# screen_sch123.net
KiCad netlist of a schematic drawn in EAGLE
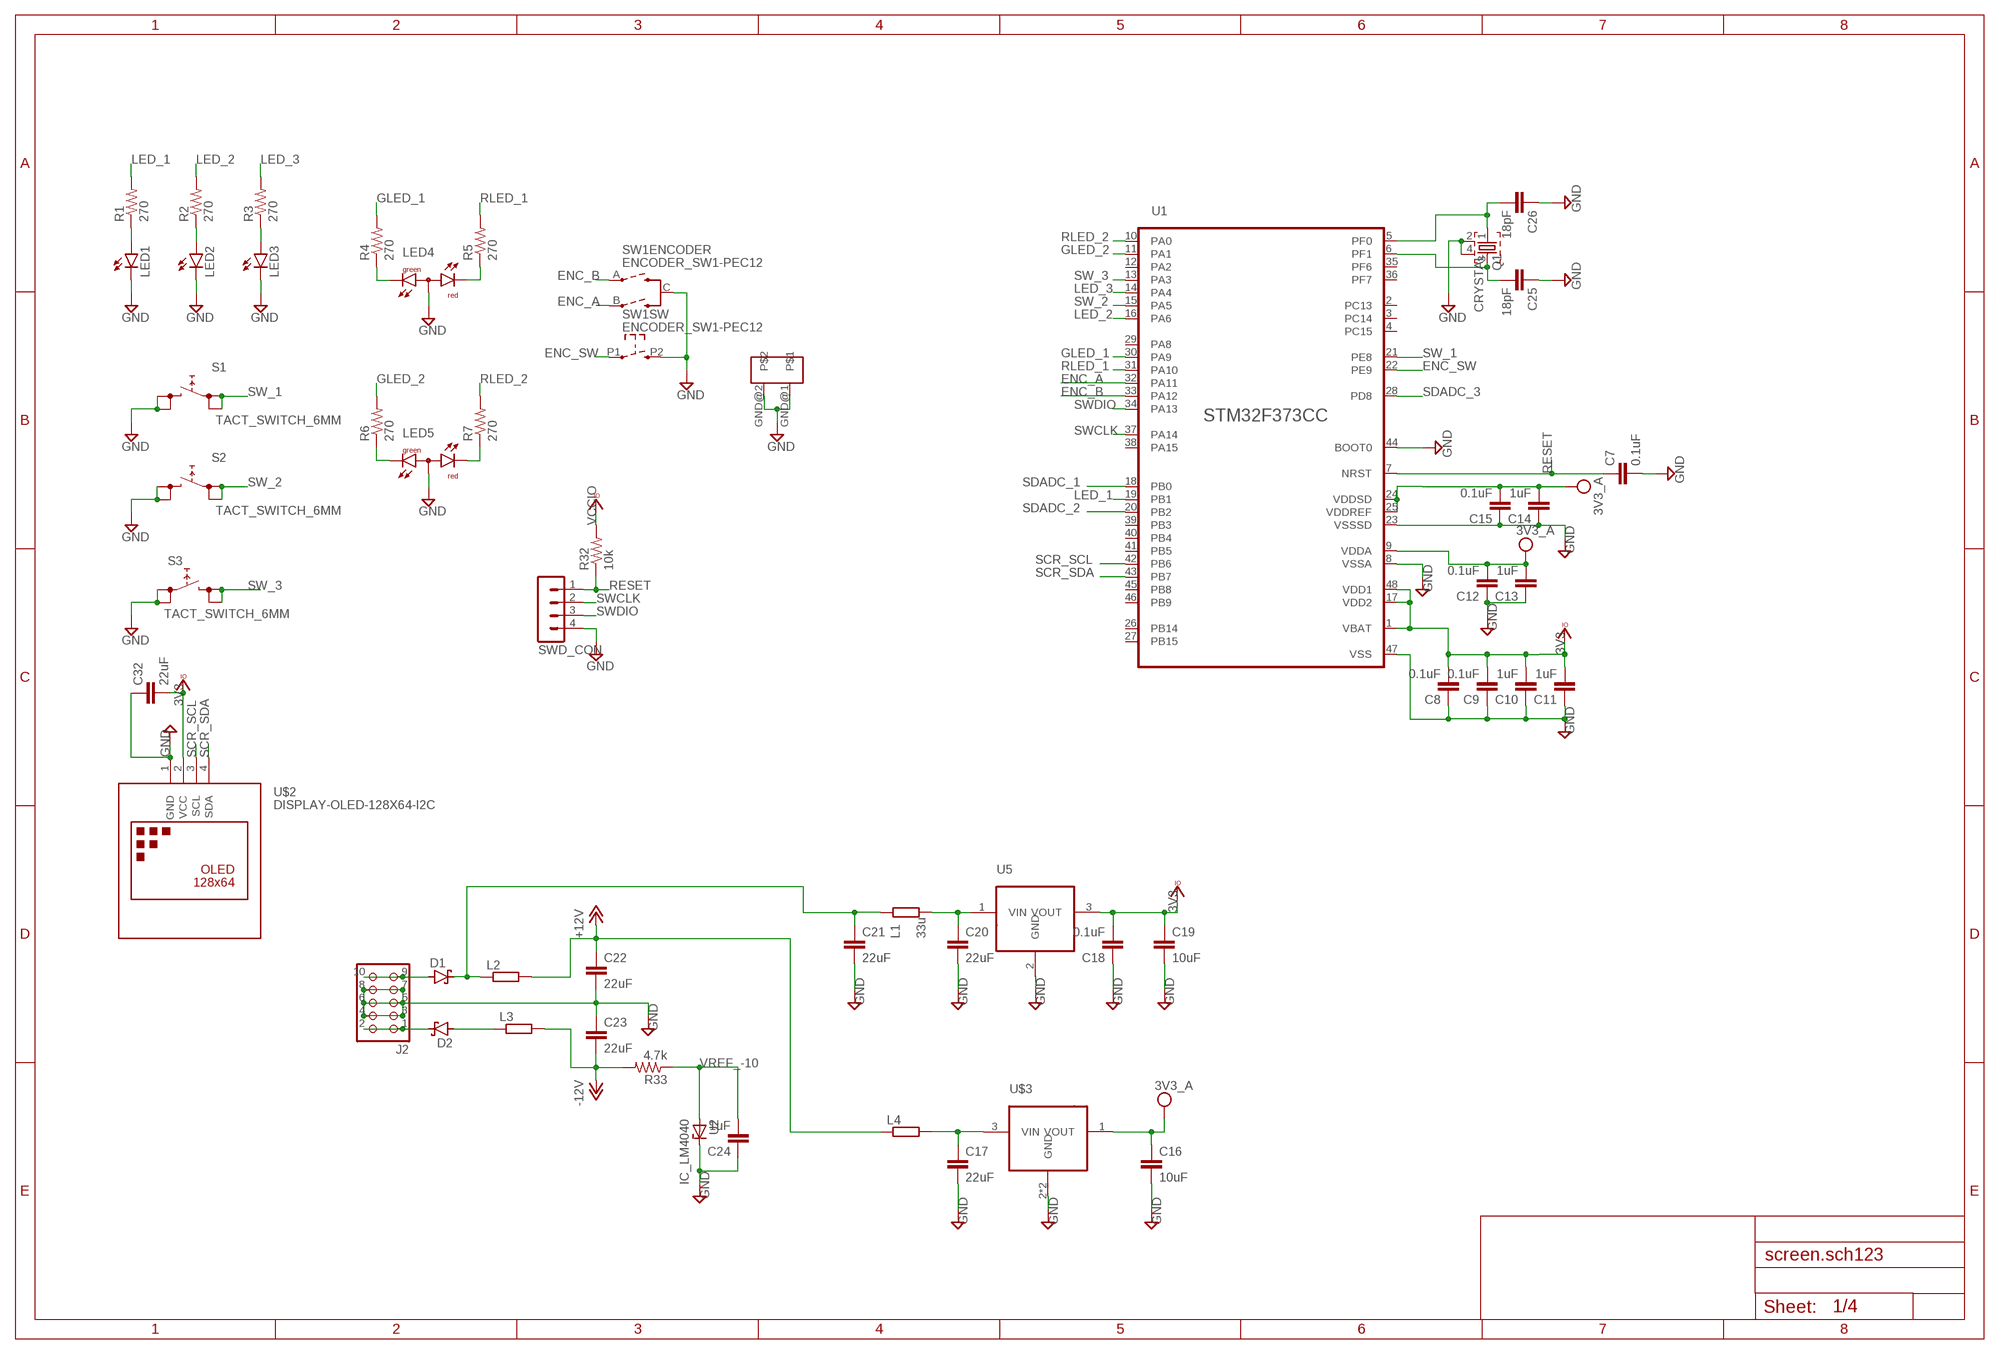
[diagram p0: schematic, sheet 1]
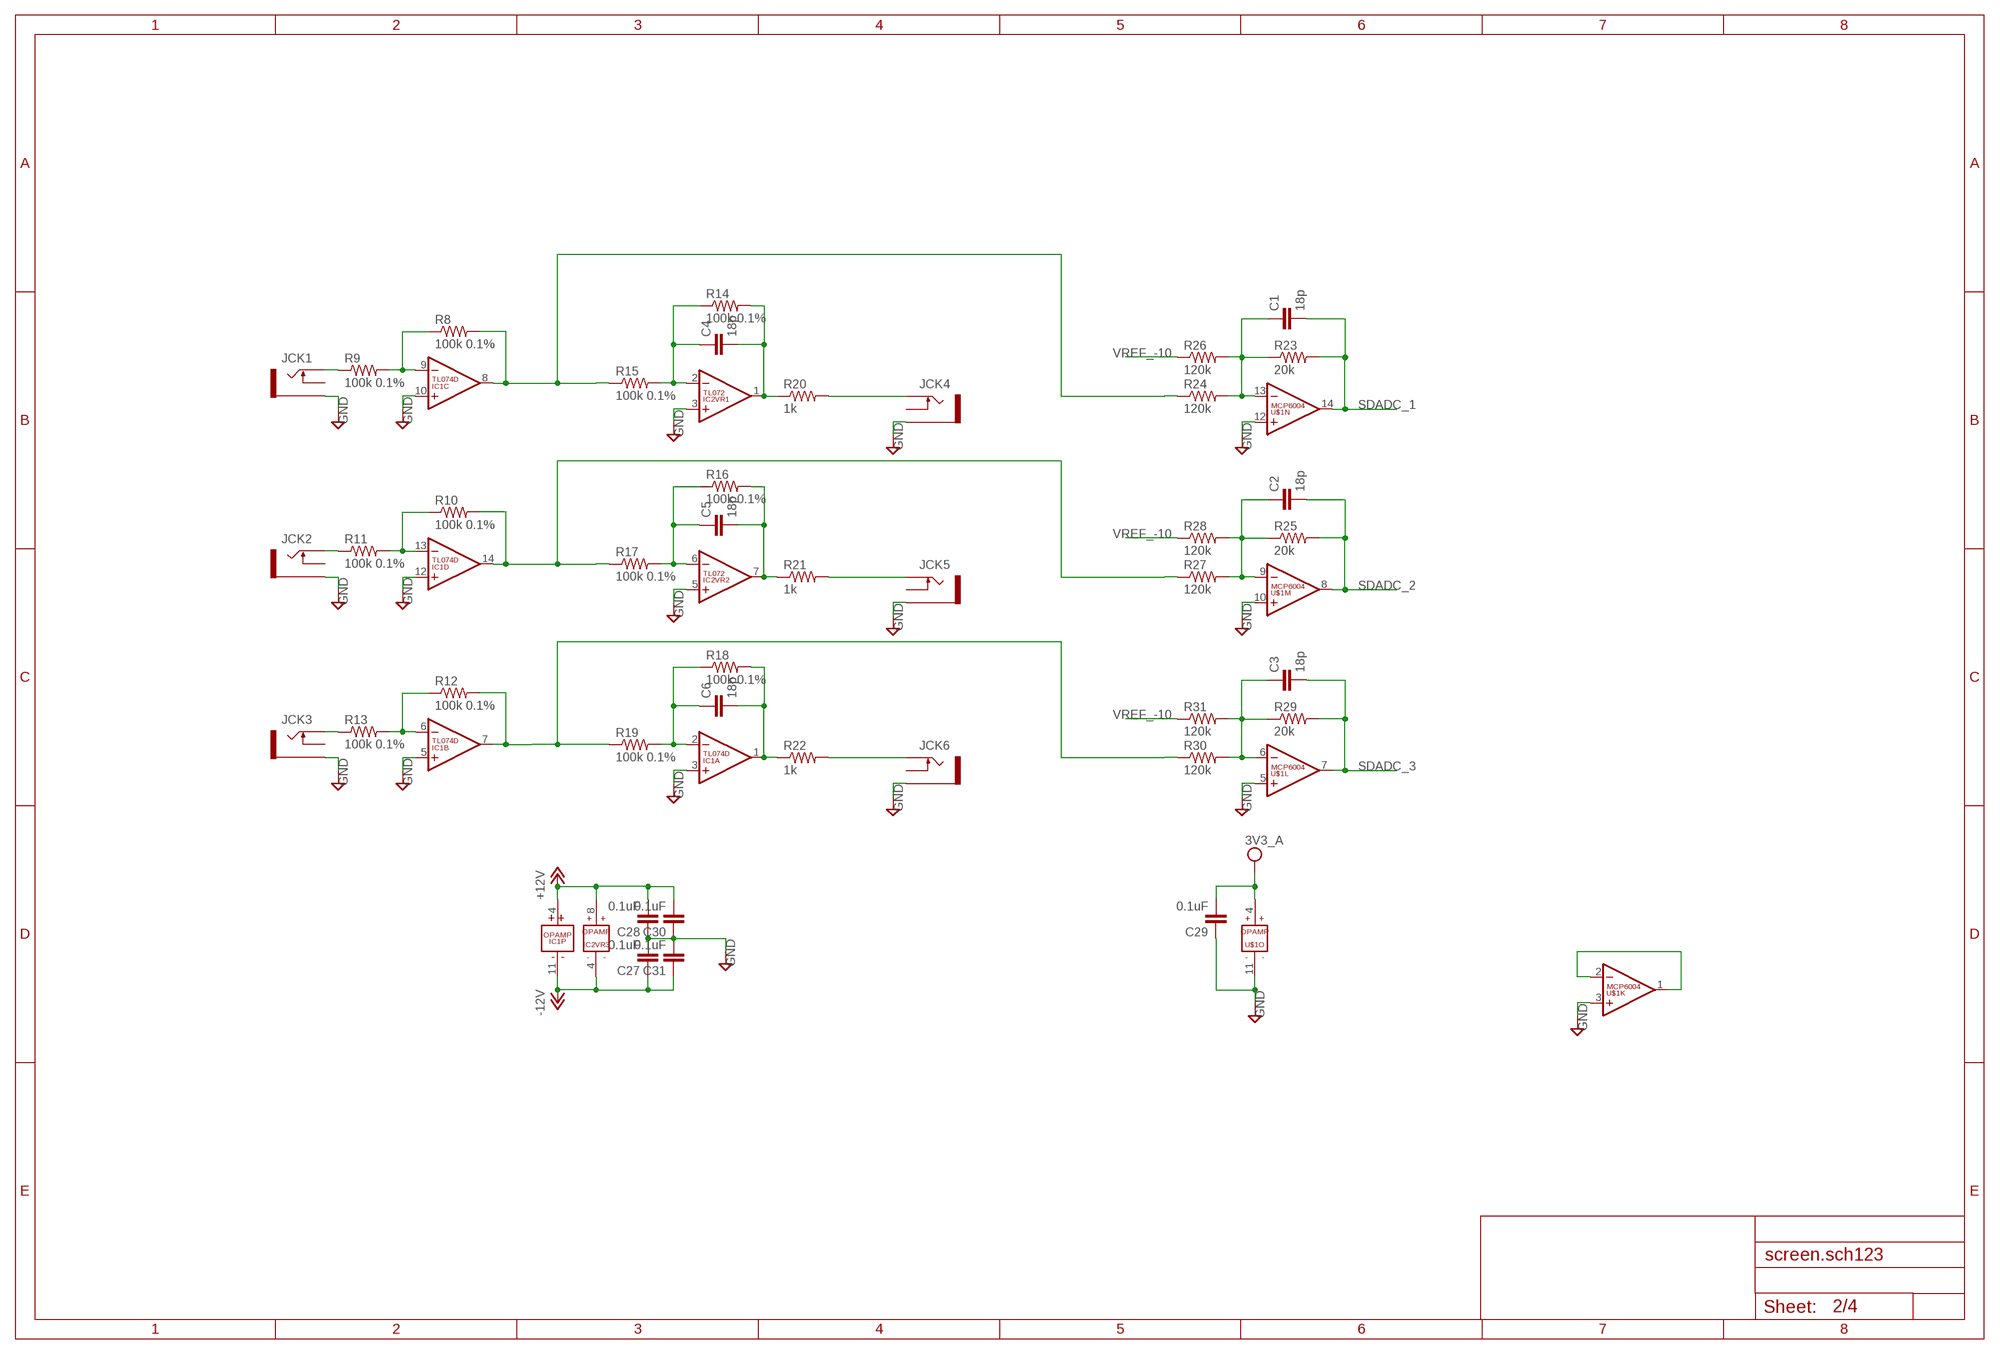
[diagram p1: schematic, sheet 2]
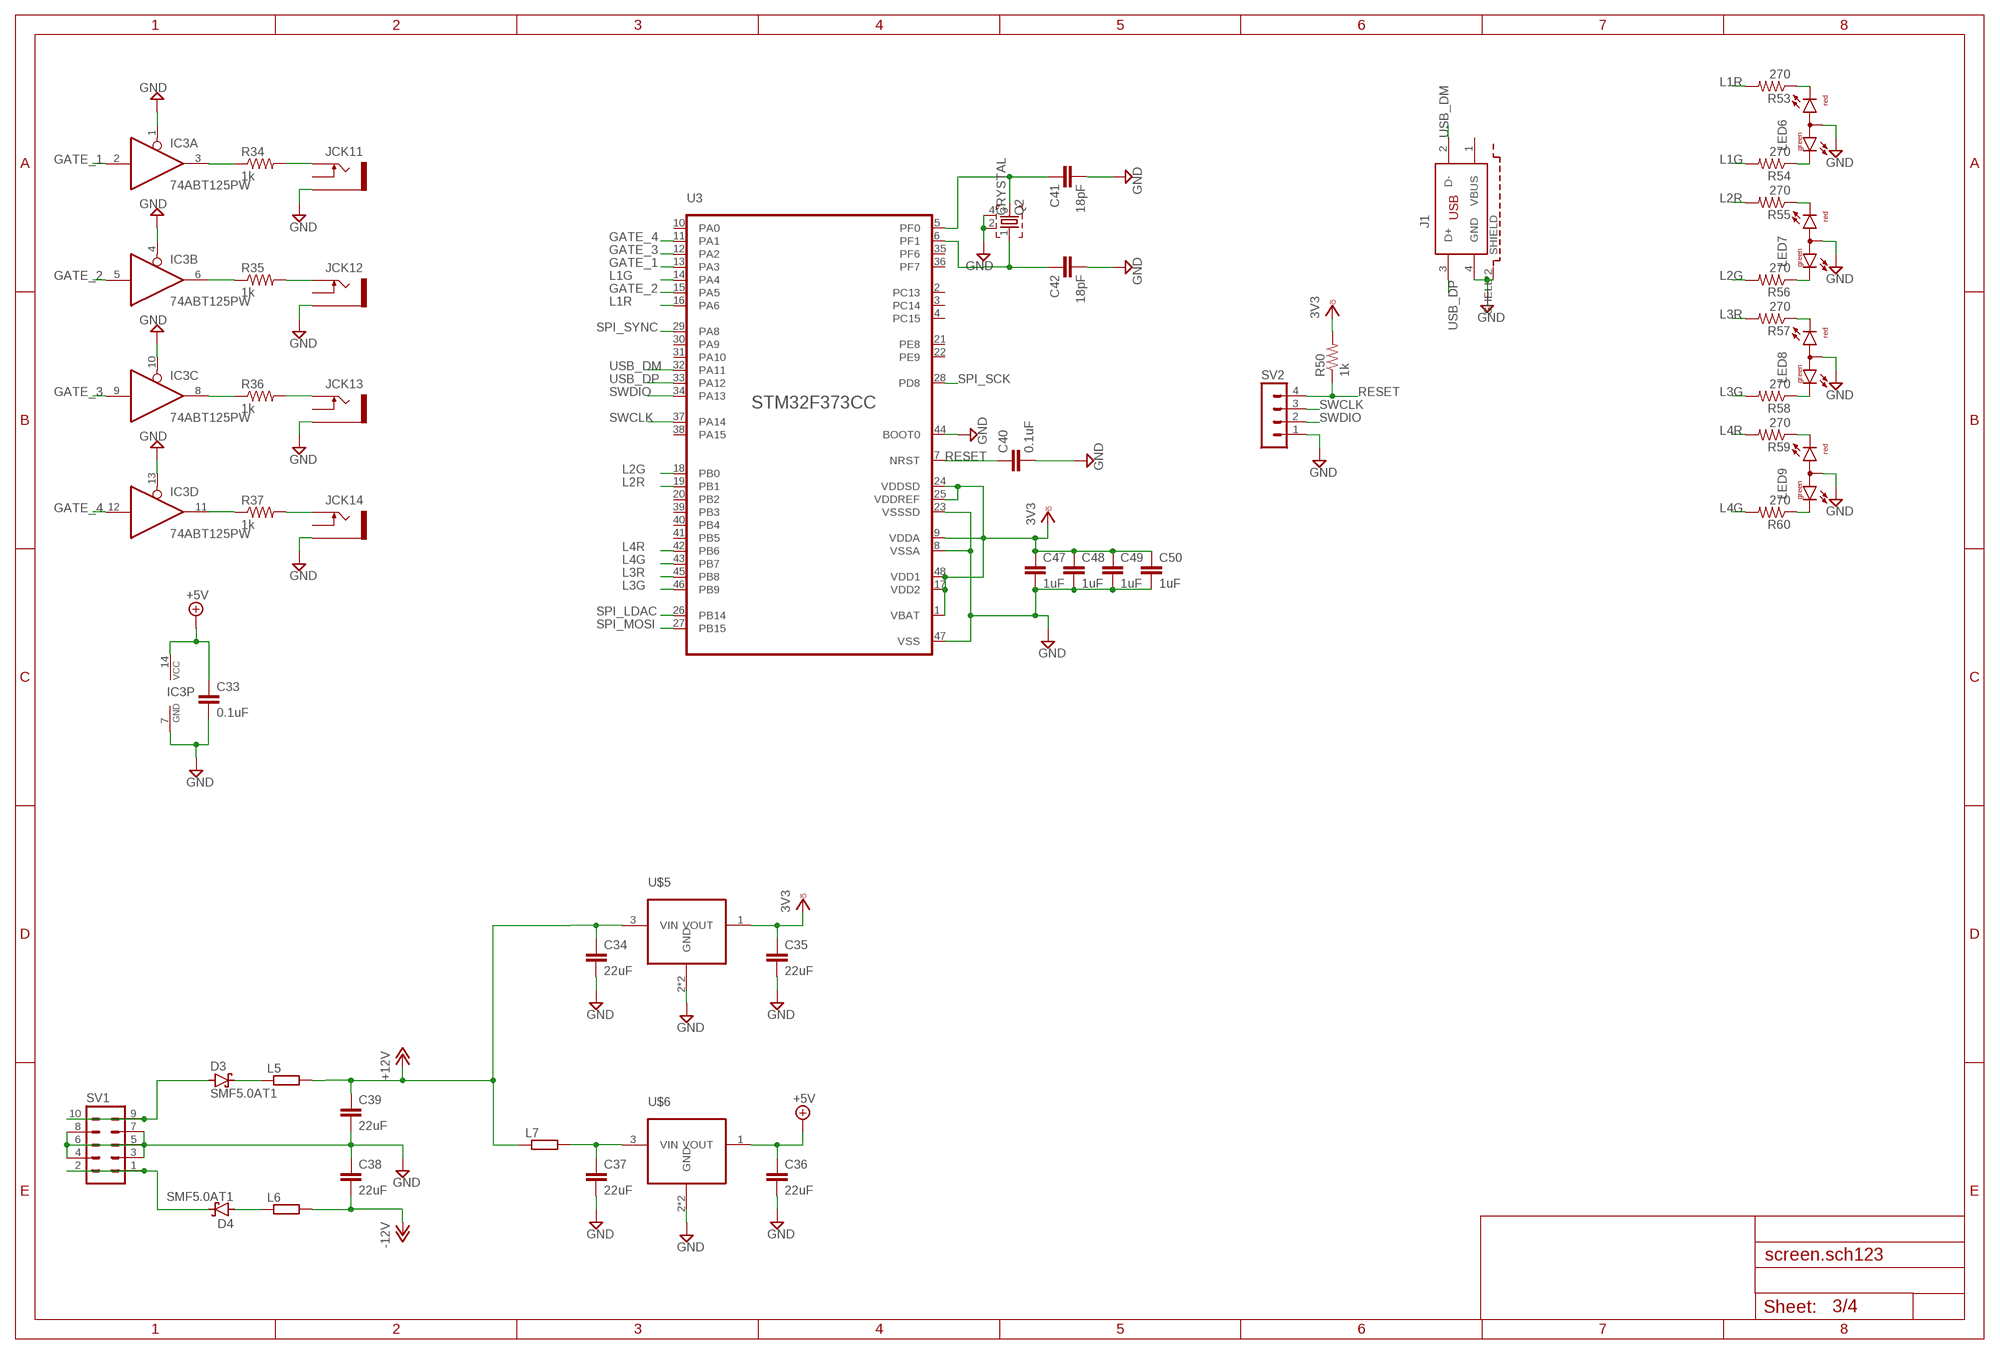
[diagram p2: schematic, sheet 3]
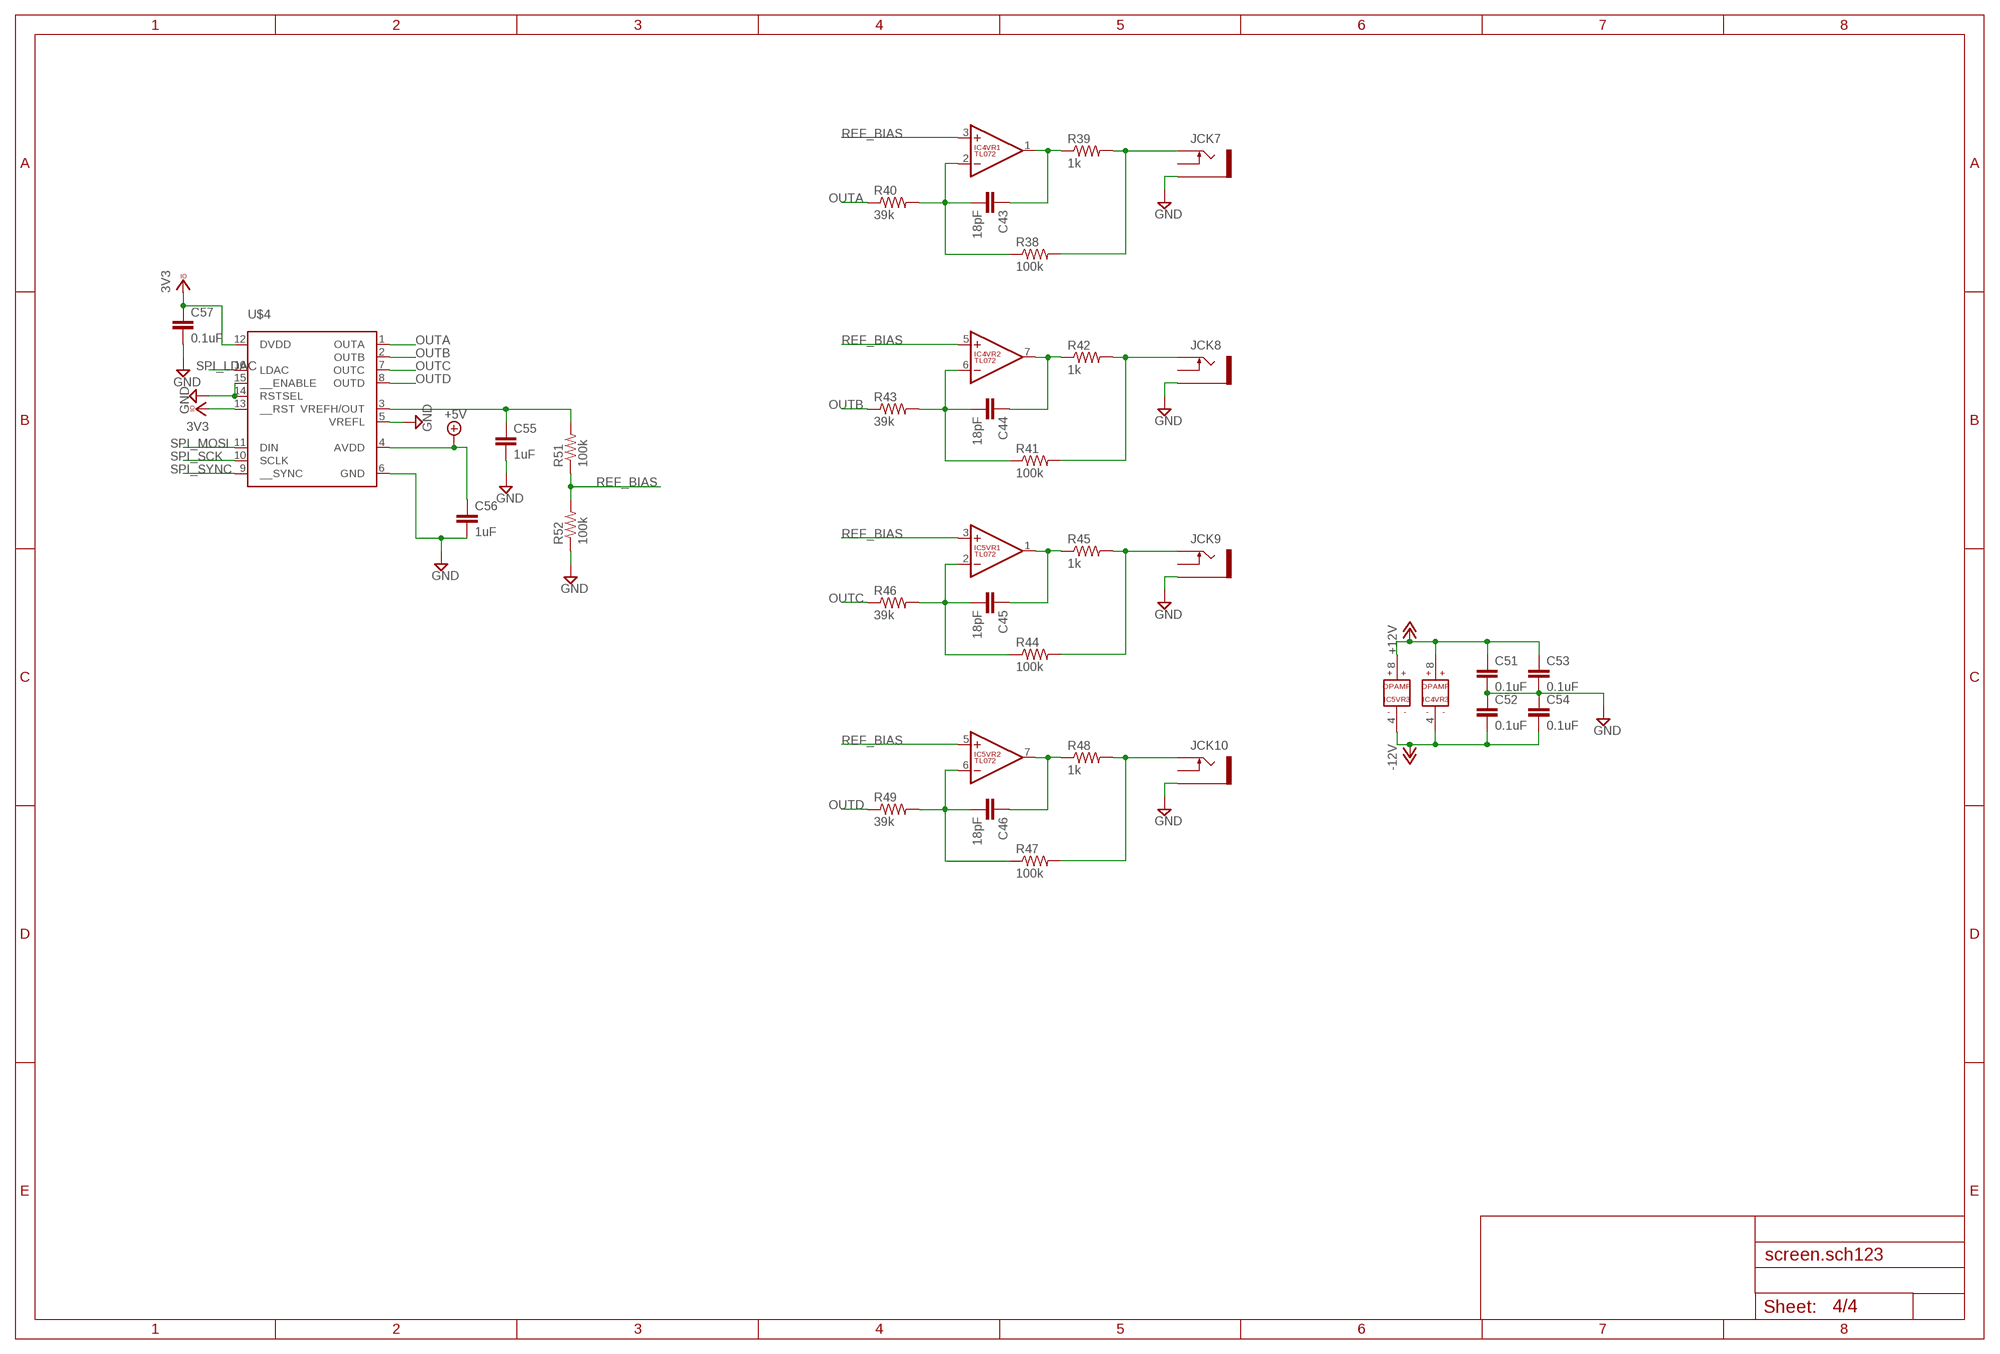
[diagram p3: schematic, sheet 4]

(export (version "E")
  (design (tool "Eeschema 10.0.6"))
  (components
    (comp (ref "C43")
      (value "18pF")
      (footprint "eagle-import:C0603K")
      (libsource (lib "eagle-import") (part "C-EUC0603K"))
    )
    (comp (ref "C44")
      (value "18pF")
      (footprint "eagle-import:C0603K")
      (libsource (lib "eagle-import") (part "C-EUC0603K"))
    )
    (comp (ref "C45")
      (value "18pF")
      (footprint "eagle-import:C0603K")
      (libsource (lib "eagle-import") (part "C-EUC0603K"))
    )
    (comp (ref "C46")
      (value "18pF")
      (footprint "eagle-import:C0603K")
      (libsource (lib "eagle-import") (part "C-EUC0603K"))
    )
    (comp (ref "C51")
      (value "0.1uF")
      (footprint "eagle-import:C0603K")
      (libsource (lib "eagle-import") (part "C-EUC0603K"))
    )
    (comp (ref "C52")
      (value "0.1uF")
      (footprint "eagle-import:C0603K")
      (libsource (lib "eagle-import") (part "C-EUC0603K"))
    )
    (comp (ref "C53")
      (value "0.1uF")
      (footprint "eagle-import:C0603K")
      (libsource (lib "eagle-import") (part "C-EUC0603K"))
    )
    (comp (ref "C54")
      (value "0.1uF")
      (footprint "eagle-import:C0603K")
      (libsource (lib "eagle-import") (part "C-EUC0603K"))
    )
    (comp (ref "C55")
      (value "1uF")
      (footprint "eagle-import:C0603K")
      (libsource (lib "eagle-import") (part "C-EUC0603K"))
    )
    (comp (ref "C56")
      (value "1uF")
      (footprint "eagle-import:C0603K")
      (libsource (lib "eagle-import") (part "C-EUC0603K"))
    )
    (comp (ref "C57")
      (value "0.1uF")
      (footprint "eagle-import:C0603K")
      (libsource (lib "eagle-import") (part "C-EUC0603K"))
    )
    (comp (ref "IC4")
      (value "TL072")
      (footprint "eagle-import:SO08")
      (libsource (lib "eagle-import") (part "TL072"))
    )
    (comp (ref "IC5")
      (value "TL072")
      (footprint "eagle-import:SO08")
      (libsource (lib "eagle-import") (part "TL072"))
    )
    (comp (ref "JCK7")
      (value "THONKICONNNEW")
      (footprint "eagle-import:WQP-PJ301M-12_JACK")
      (libsource (lib "eagle-import") (part "THONKICONNNEW"))
    )
    (comp (ref "JCK8")
      (value "THONKICONNNEW")
      (footprint "eagle-import:WQP-PJ301M-12_JACK")
      (libsource (lib "eagle-import") (part "THONKICONNNEW"))
    )
    (comp (ref "JCK9")
      (value "THONKICONNNEW")
      (footprint "eagle-import:WQP-PJ301M-12_JACK")
      (libsource (lib "eagle-import") (part "THONKICONNNEW"))
    )
    (comp (ref "JCK10")
      (value "THONKICONNNEW")
      (footprint "eagle-import:WQP-PJ301M-12_JACK")
      (libsource (lib "eagle-import") (part "THONKICONNNEW"))
    )
    (comp (ref "R38")
      (value "100k")
      (footprint "eagle-import:R0603")
      (libsource (lib "eagle-import") (part "R-US_R0603"))
    )
    (comp (ref "R39")
      (value "1k")
      (footprint "eagle-import:R0603")
      (libsource (lib "eagle-import") (part "R-US_R0603"))
    )
    (comp (ref "R40")
      (value "39k")
      (footprint "eagle-import:R0603")
      (libsource (lib "eagle-import") (part "R-US_R0603"))
    )
    (comp (ref "R41")
      (value "100k")
      (footprint "eagle-import:R0603")
      (libsource (lib "eagle-import") (part "R-US_R0603"))
    )
    (comp (ref "R42")
      (value "1k")
      (footprint "eagle-import:R0603")
      (libsource (lib "eagle-import") (part "R-US_R0603"))
    )
    (comp (ref "R43")
      (value "39k")
      (footprint "eagle-import:R0603")
      (libsource (lib "eagle-import") (part "R-US_R0603"))
    )
    (comp (ref "R44")
      (value "100k")
      (footprint "eagle-import:R0603")
      (libsource (lib "eagle-import") (part "R-US_R0603"))
    )
    (comp (ref "R45")
      (value "1k")
      (footprint "eagle-import:R0603")
      (libsource (lib "eagle-import") (part "R-US_R0603"))
    )
    (comp (ref "R46")
      (value "39k")
      (footprint "eagle-import:R0603")
      (libsource (lib "eagle-import") (part "R-US_R0603"))
    )
    (comp (ref "R47")
      (value "100k")
      (footprint "eagle-import:R0603")
      (libsource (lib "eagle-import") (part "R-US_R0603"))
    )
    (comp (ref "R48")
      (value "1k")
      (footprint "eagle-import:R0603")
      (libsource (lib "eagle-import") (part "R-US_R0603"))
    )
    (comp (ref "R49")
      (value "39k")
      (footprint "eagle-import:R0603")
      (libsource (lib "eagle-import") (part "R-US_R0603"))
    )
    (comp (ref "R51")
      (value "100k")
      (footprint "eagle-import:R0603")
      (libsource (lib "eagle-import") (part "R-US_R0603"))
    )
    (comp (ref "R52")
      (value "100k")
      (footprint "eagle-import:R0603")
      (libsource (lib "eagle-import") (part "R-US_R0603"))
    )
    (comp (ref "U$4")
      (value "DAC8565")
      (footprint "eagle-import:TSSOP16")
      (libsource (lib "eagle-import") (part "DAC8565"))
    )
    (comp (ref "C33")
      (value "0.1uF")
      (footprint "eagle-import:C0603K")
      (libsource (lib "eagle-import") (part "C-EUC0603K"))
    )
    (comp (ref "C34")
      (value "22uF")
      (footprint "eagle-import:C1206K")
      (libsource (lib "eagle-import") (part "C-EUC1206K"))
    )
    (comp (ref "C35")
      (value "22uF")
      (footprint "eagle-import:C1206K")
      (libsource (lib "eagle-import") (part "C-EUC1206K"))
    )
    (comp (ref "C36")
      (value "22uF")
      (footprint "eagle-import:C1206K")
      (libsource (lib "eagle-import") (part "C-EUC1206K"))
    )
    (comp (ref "C37")
      (value "22uF")
      (footprint "eagle-import:C1206K")
      (libsource (lib "eagle-import") (part "C-EUC1206K"))
    )
    (comp (ref "C38")
      (value "22uF")
      (footprint "eagle-import:C1206K")
      (libsource (lib "eagle-import") (part "C-EUC1206K"))
    )
    (comp (ref "C39")
      (value "22uF")
      (footprint "eagle-import:C1206K")
      (libsource (lib "eagle-import") (part "C-EUC1206K"))
    )
    (comp (ref "C40")
      (value "0.1uF")
      (footprint "eagle-import:C0603K")
      (libsource (lib "eagle-import") (part "C-EUC0603K"))
    )
    (comp (ref "C41")
      (value "18pF")
      (footprint "eagle-import:C0603K")
      (libsource (lib "eagle-import") (part "C-EUC0603K"))
    )
    (comp (ref "C42")
      (value "18pF")
      (footprint "eagle-import:C0603K")
      (libsource (lib "eagle-import") (part "C-EUC0603K"))
    )
    (comp (ref "C47")
      (value "1uF")
      (footprint "eagle-import:C0603K")
      (libsource (lib "eagle-import") (part "C-EUC0603K"))
    )
    (comp (ref "C48")
      (value "1uF")
      (footprint "eagle-import:C0603K")
      (libsource (lib "eagle-import") (part "C-EUC0603K"))
    )
    (comp (ref "C49")
      (value "1uF")
      (footprint "eagle-import:C0603K")
      (libsource (lib "eagle-import") (part "C-EUC0603K"))
    )
    (comp (ref "C50")
      (value "1uF")
      (footprint "eagle-import:C0603K")
      (libsource (lib "eagle-import") (part "C-EUC0603K"))
    )
    (comp (ref "D3")
      (value "SMF5.0AT1")
      (footprint "eagle-import:SOD123FL")
      (libsource (lib "eagle-import") (part "SMF5.0AT1"))
    )
    (comp (ref "D4")
      (value "SMF5.0AT1")
      (footprint "eagle-import:SOD123FL")
      (libsource (lib "eagle-import") (part "SMF5.0AT1"))
    )
    (comp (ref "IC3")
      (value "74ABT125PW")
      (footprint "eagle-import:TSSOP14")
      (libsource (lib "eagle-import") (part "74125PWABT"))
    )
    (comp (ref "J1")
      (value "61400413321")
      (footprint "eagle-import:61400413321")
      (libsource (lib "eagle-import") (part "61400413321"))
    )
    (comp (ref "JCK11")
      (value "THONKICONNNEW")
      (footprint "eagle-import:WQP-PJ301M-12_JACK")
      (libsource (lib "eagle-import") (part "THONKICONNNEW"))
    )
    (comp (ref "JCK12")
      (value "THONKICONNNEW")
      (footprint "eagle-import:WQP-PJ301M-12_JACK")
      (libsource (lib "eagle-import") (part "THONKICONNNEW"))
    )
    (comp (ref "JCK13")
      (value "THONKICONNNEW")
      (footprint "eagle-import:WQP-PJ301M-12_JACK")
      (libsource (lib "eagle-import") (part "THONKICONNNEW"))
    )
    (comp (ref "JCK14")
      (value "THONKICONNNEW")
      (footprint "eagle-import:WQP-PJ301M-12_JACK")
      (libsource (lib "eagle-import") (part "THONKICONNNEW"))
    )
    (comp (ref "L5")
      (value "R-EU_R0603")
      (footprint "eagle-import:R0603")
      (libsource (lib "eagle-import") (part "R-EU_R0603"))
    )
    (comp (ref "L6")
      (value "R-EU_R0603")
      (footprint "eagle-import:R0603")
      (libsource (lib "eagle-import") (part "R-EU_R0603"))
    )
    (comp (ref "L7")
      (value "R-EU_R0603")
      (footprint "eagle-import:R0603")
      (libsource (lib "eagle-import") (part "R-EU_R0603"))
    )
    (comp (ref "LED6")
      (value "L-115WEGW-CA")
      (footprint "eagle-import:DUOLED-A-3MM")
      (libsource (lib "eagle-import") (part "L-115WEGW-CA"))
    )
    (comp (ref "LED7")
      (value "L-115WEGW-CA")
      (footprint "eagle-import:DUOLED-A-3MM")
      (libsource (lib "eagle-import") (part "L-115WEGW-CA"))
    )
    (comp (ref "LED8")
      (value "L-115WEGW-CA")
      (footprint "eagle-import:DUOLED-A-3MM")
      (libsource (lib "eagle-import") (part "L-115WEGW-CA"))
    )
    (comp (ref "LED9")
      (value "L-115WEGW-CA")
      (footprint "eagle-import:DUOLED-A-3MM")
      (libsource (lib "eagle-import") (part "L-115WEGW-CA"))
    )
    (comp (ref "Q2")
      (value "CRYSTAL")
      (footprint "eagle-import:CTS406")
      (libsource (lib "eagle-import") (part "CRYSTAL"))
    )
    (comp (ref "R34")
      (value "1k")
      (footprint "eagle-import:R0603")
      (libsource (lib "eagle-import") (part "R-US_R0603"))
    )
    (comp (ref "R35")
      (value "1k")
      (footprint "eagle-import:R0603")
      (libsource (lib "eagle-import") (part "R-US_R0603"))
    )
    (comp (ref "R36")
      (value "1k")
      (footprint "eagle-import:R0603")
      (libsource (lib "eagle-import") (part "R-US_R0603"))
    )
    (comp (ref "R37")
      (value "1k")
      (footprint "eagle-import:R0603")
      (libsource (lib "eagle-import") (part "R-US_R0603"))
    )
    (comp (ref "R50")
      (value "1k")
      (footprint "eagle-import:R0603")
      (libsource (lib "eagle-import") (part "R-US_R0603"))
    )
    (comp (ref "R53")
      (value "270")
      (footprint "eagle-import:R0603")
      (libsource (lib "eagle-import") (part "R-US_R0603"))
    )
    (comp (ref "R54")
      (value "270")
      (footprint "eagle-import:R0603")
      (libsource (lib "eagle-import") (part "R-US_R0603"))
    )
    (comp (ref "R55")
      (value "270")
      (footprint "eagle-import:R0603")
      (libsource (lib "eagle-import") (part "R-US_R0603"))
    )
    (comp (ref "R56")
      (value "270")
      (footprint "eagle-import:R0603")
      (libsource (lib "eagle-import") (part "R-US_R0603"))
    )
    (comp (ref "R57")
      (value "270")
      (footprint "eagle-import:R0603")
      (libsource (lib "eagle-import") (part "R-US_R0603"))
    )
    (comp (ref "R58")
      (value "270")
      (footprint "eagle-import:R0603")
      (libsource (lib "eagle-import") (part "R-US_R0603"))
    )
    (comp (ref "R59")
      (value "270")
      (footprint "eagle-import:R0603")
      (libsource (lib "eagle-import") (part "R-US_R0603"))
    )
    (comp (ref "R60")
      (value "270")
      (footprint "eagle-import:R0603")
      (libsource (lib "eagle-import") (part "R-US_R0603"))
    )
    (comp (ref "SV1")
      (value "MA05-2")
      (footprint "eagle-import:MA05-2")
      (libsource (lib "eagle-import") (part "MA05-2"))
    )
    (comp (ref "SV2")
      (value "MA04-1")
      (footprint "eagle-import:MA04-1")
      (libsource (lib "eagle-import") (part "MA04-1"))
    )
    (comp (ref "U$5")
      (value "LD2981ABUSOT89")
      (footprint "eagle-import:SOT89")
      (libsource (lib "eagle-import") (part "LD2981ABUSOT89"))
    )
    (comp (ref "U$6")
      (value "LD2981ABUSOT89")
      (footprint "eagle-import:SOT89")
      (libsource (lib "eagle-import") (part "LD2981ABUSOT89"))
    )
    (comp (ref "U3")
      (value "STM32F373LQFP48")
      (footprint "eagle-import:LQFP48")
      (libsource (lib "eagle-import") (part "STM32F373LQFP48"))
    )
    (comp (ref "C7")
      (value "0.1uF")
      (footprint "eagle-import:C0603")
      (libsource (lib "eagle-import") (part "C-EUC0603"))
    )
    (comp (ref "C8")
      (value "0.1uF")
      (footprint "eagle-import:C0603")
      (libsource (lib "eagle-import") (part "C-EUC0603"))
    )
    (comp (ref "C9")
      (value "0.1uF")
      (footprint "eagle-import:C0603")
      (libsource (lib "eagle-import") (part "C-EUC0603"))
    )
    (comp (ref "C10")
      (value "1uF")
      (footprint "eagle-import:C0603")
      (libsource (lib "eagle-import") (part "C-EUC0603"))
    )
    (comp (ref "C11")
      (value "1uF")
      (footprint "eagle-import:C0603")
      (libsource (lib "eagle-import") (part "C-EUC0603"))
    )
    (comp (ref "C12")
      (value "0.1uF")
      (footprint "eagle-import:C0603")
      (libsource (lib "eagle-import") (part "C-EUC0603"))
    )
    (comp (ref "C13")
      (value "1uF")
      (footprint "eagle-import:C0603")
      (libsource (lib "eagle-import") (part "C-EUC0603"))
    )
    (comp (ref "C14")
      (value "1uF")
      (footprint "eagle-import:C0603")
      (libsource (lib "eagle-import") (part "C-EUC0603"))
    )
    (comp (ref "C15")
      (value "0.1uF")
      (footprint "eagle-import:C0603")
      (libsource (lib "eagle-import") (part "C-EUC0603"))
    )
    (comp (ref "C16")
      (value "10uF")
      (footprint "eagle-import:C1206")
      (libsource (lib "eagle-import") (part "C-EUC1206"))
    )
    (comp (ref "C17")
      (value "22uF")
      (footprint "eagle-import:C1206")
      (libsource (lib "eagle-import") (part "C-EUC1206"))
    )
    (comp (ref "C18")
      (value "0.1uF")
      (footprint "eagle-import:C0603")
      (libsource (lib "eagle-import") (part "C-EUC0603"))
    )
    (comp (ref "C19")
      (value "10uF")
      (footprint "eagle-import:C1206")
      (libsource (lib "eagle-import") (part "C-EUC1206"))
    )
    (comp (ref "C20")
      (value "22uF")
      (footprint "eagle-import:C1206")
      (libsource (lib "eagle-import") (part "C-EUC1206"))
    )
    (comp (ref "C21")
      (value "22uF")
      (footprint "eagle-import:C1206")
      (libsource (lib "eagle-import") (part "C-EUC1206"))
    )
    (comp (ref "C22")
      (value "22uF")
      (footprint "eagle-import:C1206")
      (libsource (lib "eagle-import") (part "C-EUC1206"))
    )
    (comp (ref "C23")
      (value "22uF")
      (footprint "eagle-import:C1206")
      (libsource (lib "eagle-import") (part "C-EUC1206"))
    )
    (comp (ref "C24")
      (value "1uF")
      (footprint "eagle-import:C0603")
      (libsource (lib "eagle-import") (part "C-EUC0603"))
    )
    (comp (ref "C25")
      (value "18pF")
      (footprint "eagle-import:C0603")
      (libsource (lib "eagle-import") (part "C-EUC0603"))
    )
    (comp (ref "C26")
      (value "18pF")
      (footprint "eagle-import:C0603")
      (libsource (lib "eagle-import") (part "C-EUC0603"))
    )
    (comp (ref "C32")
      (value "22uF")
      (footprint "eagle-import:C1206")
      (libsource (lib "eagle-import") (part "C-EUC1206"))
    )
    (comp (ref "D1")
      (value "SMF5.0AT1")
      (footprint "eagle-import:SOD123FL")
      (libsource (lib "eagle-import") (part "SMF5.0AT1"))
    )
    (comp (ref "D2")
      (value "SMF5.0AT1")
      (footprint "eagle-import:SOD123FL")
      (libsource (lib "eagle-import") (part "SMF5.0AT1"))
    )
    (comp (ref "J2")
      (value "CON_HEADER_2X05-PTH+SHROUDED_A")
      (footprint "eagle-import:PINSHRD_PTH_2X05")
      (libsource (lib "eagle-import") (part "CON_HEADER_2X05-PTH+SHROUDED_A"))
    )
    (comp (ref "L1")
      (value "33u")
      (footprint "eagle-import:R0805")
      (libsource (lib "eagle-import") (part "R-EU_R0805"))
    )
    (comp (ref "L2")
      (value "R-EU_R0603")
      (footprint "eagle-import:R0603")
      (libsource (lib "eagle-import") (part "R-EU_R0603"))
    )
    (comp (ref "L3")
      (value "R-EU_R0603")
      (footprint "eagle-import:R0603")
      (libsource (lib "eagle-import") (part "R-EU_R0603"))
    )
    (comp (ref "L4")
      (value "R-EU_R0603")
      (footprint "eagle-import:R0603")
      (libsource (lib "eagle-import") (part "R-EU_R0603"))
    )
    (comp (ref "LED1")
      (value "LED3MM")
      (footprint "eagle-import:LED3MM")
      (libsource (lib "eagle-import") (part "LED3MM"))
    )
    (comp (ref "LED2")
      (value "LED3MM")
      (footprint "eagle-import:LED3MM")
      (libsource (lib "eagle-import") (part "LED3MM"))
    )
    (comp (ref "LED3")
      (value "LED3MM")
      (footprint "eagle-import:LED3MM")
      (libsource (lib "eagle-import") (part "LED3MM"))
    )
    (comp (ref "LED4")
      (value "L-115WEGW-CA")
      (footprint "eagle-import:DUOLED-A-3MM")
      (libsource (lib "eagle-import") (part "L-115WEGW-CA"))
    )
    (comp (ref "LED5")
      (value "L-115WEGW-CA")
      (footprint "eagle-import:DUOLED-A-3MM")
      (libsource (lib "eagle-import") (part "L-115WEGW-CA"))
    )
    (comp (ref "Q1")
      (value "CRYSTAL")
      (footprint "eagle-import:CTS406")
      (libsource (lib "eagle-import") (part "CRYSTAL"))
    )
    (comp (ref "R1")
      (value "270")
      (footprint "eagle-import:R0603")
      (libsource (lib "eagle-import") (part "R-US_R0603"))
    )
    (comp (ref "R2")
      (value "270")
      (footprint "eagle-import:R0603")
      (libsource (lib "eagle-import") (part "R-US_R0603"))
    )
    (comp (ref "R3")
      (value "270")
      (footprint "eagle-import:R0603")
      (libsource (lib "eagle-import") (part "R-US_R0603"))
    )
    (comp (ref "R4")
      (value "270")
      (footprint "eagle-import:R0603")
      (libsource (lib "eagle-import") (part "R-US_R0603"))
    )
    (comp (ref "R5")
      (value "270")
      (footprint "eagle-import:R0603")
      (libsource (lib "eagle-import") (part "R-US_R0603"))
    )
    (comp (ref "R6")
      (value "270")
      (footprint "eagle-import:R0603")
      (libsource (lib "eagle-import") (part "R-US_R0603"))
    )
    (comp (ref "R7")
      (value "270")
      (footprint "eagle-import:R0603")
      (libsource (lib "eagle-import") (part "R-US_R0603"))
    )
    (comp (ref "R32")
      (value "10k")
      (footprint "eagle-import:R0603")
      (libsource (lib "eagle-import") (part "R-US_R0603"))
    )
    (comp (ref "R33")
      (value "4.7k")
      (footprint "eagle-import:R0603")
      (libsource (lib "eagle-import") (part "R-US_R0603"))
    )
    (comp (ref "S1")
      (value "TACT_SWITCH_6MM")
      (footprint "eagle-import:TACT_SWITCH_6MM")
      (libsource (lib "eagle-import") (part "TACT_SWITCH_6MM"))
    )
    (comp (ref "S2")
      (value "TACT_SWITCH_6MM")
      (footprint "eagle-import:TACT_SWITCH_6MM")
      (libsource (lib "eagle-import") (part "TACT_SWITCH_6MM"))
    )
    (comp (ref "S3")
      (value "TACT_SWITCH_6MM")
      (footprint "eagle-import:TACT_SWITCH_6MM")
      (libsource (lib "eagle-import") (part "TACT_SWITCH_6MM"))
    )
    (comp (ref "SW1")
      (value "ENCODER_SW1-PEC12")
      (footprint "eagle-import:PEC12_INCREMENTAL_ENCODER")
      (libsource (lib "eagle-import") (part "ENCODER_SW1-PEC12"))
    )
    (comp (ref "SWD_CON")
      (value "MA04-1")
      (footprint "eagle-import:MA04-1")
      (libsource (lib "eagle-import") (part "MA04-1"))
    )
    (comp (ref "U$2")
      (value "DISPLAY-OLED-128X64-I2C")
      (footprint "eagle-import:DISPLAY-OLED-128X64-I2C")
      (libsource (lib "eagle-import") (part "DISPLAY-OLED-128X64-I2C"))
    )
    (comp (ref "U$3")
      (value "LD2981ABUSOT89")
      (footprint "eagle-import:SOT89")
      (libsource (lib "eagle-import") (part "LD2981ABUSOT89"))
    )
    (comp (ref "U1")
      (value "STM32F373LQFP48")
      (footprint "eagle-import:LQFP48")
      (libsource (lib "eagle-import") (part "STM32F373LQFP48"))
    )
    (comp (ref "U2")
      (value "IC_LM4040")
      (footprint "eagle-import:SOT-23")
      (libsource (lib "eagle-import") (part "IC_LM4040"))
    )
    (comp (ref "U5")
      (value "R-78E-0.5")
      (footprint "eagle-import:TO-220_RECOM")
      (libsource (lib "eagle-import") (part "R-78E-0.5"))
    )
    (comp (ref "C1")
      (value "18p")
      (footprint "eagle-import:C0603")
      (libsource (lib "eagle-import") (part "C-EUC0603"))
    )
    (comp (ref "C2")
      (value "18p")
      (footprint "eagle-import:C0603")
      (libsource (lib "eagle-import") (part "C-EUC0603"))
    )
    (comp (ref "C3")
      (value "18p")
      (footprint "eagle-import:C0603")
      (libsource (lib "eagle-import") (part "C-EUC0603"))
    )
    (comp (ref "C4")
      (value "18p")
      (footprint "eagle-import:C0603")
      (libsource (lib "eagle-import") (part "C-EUC0603"))
    )
    (comp (ref "C5")
      (value "18p")
      (footprint "eagle-import:C0603")
      (libsource (lib "eagle-import") (part "C-EUC0603"))
    )
    (comp (ref "C6")
      (value "18p")
      (footprint "eagle-import:C0603")
      (libsource (lib "eagle-import") (part "C-EUC0603"))
    )
    (comp (ref "C27")
      (value "0.1uF")
      (footprint "eagle-import:C0603")
      (libsource (lib "eagle-import") (part "C-EUC0603"))
    )
    (comp (ref "C28")
      (value "0.1uF")
      (footprint "eagle-import:C0603")
      (libsource (lib "eagle-import") (part "C-EUC0603"))
    )
    (comp (ref "C29")
      (value "0.1uF")
      (footprint "eagle-import:C0603")
      (libsource (lib "eagle-import") (part "C-EUC0603"))
    )
    (comp (ref "C30")
      (value "0.1uF")
      (footprint "eagle-import:C0603")
      (libsource (lib "eagle-import") (part "C-EUC0603"))
    )
    (comp (ref "C31")
      (value "0.1uF")
      (footprint "eagle-import:C0603")
      (libsource (lib "eagle-import") (part "C-EUC0603"))
    )
    (comp (ref "IC1")
      (value "TL074D")
      (footprint "eagle-import:SO14")
      (libsource (lib "eagle-import") (part "TL074D"))
    )
    (comp (ref "IC2")
      (value "TL072")
      (footprint "eagle-import:SO08")
      (libsource (lib "eagle-import") (part "TL072"))
    )
    (comp (ref "JCK1")
      (value "THONKICONNNEW")
      (footprint "eagle-import:WQP-PJ301M-12_JACK")
      (libsource (lib "eagle-import") (part "THONKICONNNEW"))
    )
    (comp (ref "JCK2")
      (value "THONKICONNNEW")
      (footprint "eagle-import:WQP-PJ301M-12_JACK")
      (libsource (lib "eagle-import") (part "THONKICONNNEW"))
    )
    (comp (ref "JCK3")
      (value "THONKICONNNEW")
      (footprint "eagle-import:WQP-PJ301M-12_JACK")
      (libsource (lib "eagle-import") (part "THONKICONNNEW"))
    )
    (comp (ref "JCK4")
      (value "THONKICONNNEW")
      (footprint "eagle-import:WQP-PJ301M-12_JACK")
      (libsource (lib "eagle-import") (part "THONKICONNNEW"))
    )
    (comp (ref "JCK5")
      (value "THONKICONNNEW")
      (footprint "eagle-import:WQP-PJ301M-12_JACK")
      (libsource (lib "eagle-import") (part "THONKICONNNEW"))
    )
    (comp (ref "JCK6")
      (value "THONKICONNNEW")
      (footprint "eagle-import:WQP-PJ301M-12_JACK")
      (libsource (lib "eagle-import") (part "THONKICONNNEW"))
    )
    (comp (ref "R8")
      (value "100k 0.1%")
      (footprint "eagle-import:R0603")
      (libsource (lib "eagle-import") (part "R-US_R0603"))
    )
    (comp (ref "R9")
      (value "100k 0.1%")
      (footprint "eagle-import:R0603")
      (libsource (lib "eagle-import") (part "R-US_R0603"))
    )
    (comp (ref "R10")
      (value "100k 0.1%")
      (footprint "eagle-import:R0603")
      (libsource (lib "eagle-import") (part "R-US_R0603"))
    )
    (comp (ref "R11")
      (value "100k 0.1%")
      (footprint "eagle-import:R0603")
      (libsource (lib "eagle-import") (part "R-US_R0603"))
    )
    (comp (ref "R12")
      (value "100k 0.1%")
      (footprint "eagle-import:R0603")
      (libsource (lib "eagle-import") (part "R-US_R0603"))
    )
    (comp (ref "R13")
      (value "100k 0.1%")
      (footprint "eagle-import:R0603")
      (libsource (lib "eagle-import") (part "R-US_R0603"))
    )
    (comp (ref "R14")
      (value "100k 0.1%")
      (footprint "eagle-import:R0603")
      (libsource (lib "eagle-import") (part "R-US_R0603"))
    )
    (comp (ref "R15")
      (value "100k 0.1%")
      (footprint "eagle-import:R0603")
      (libsource (lib "eagle-import") (part "R-US_R0603"))
    )
    (comp (ref "R16")
      (value "100k 0.1%")
      (footprint "eagle-import:R0603")
      (libsource (lib "eagle-import") (part "R-US_R0603"))
    )
    (comp (ref "R17")
      (value "100k 0.1%")
      (footprint "eagle-import:R0603")
      (libsource (lib "eagle-import") (part "R-US_R0603"))
    )
    (comp (ref "R18")
      (value "100k 0.1%")
      (footprint "eagle-import:R0603")
      (libsource (lib "eagle-import") (part "R-US_R0603"))
    )
    (comp (ref "R19")
      (value "100k 0.1%")
      (footprint "eagle-import:R0603")
      (libsource (lib "eagle-import") (part "R-US_R0603"))
    )
    (comp (ref "R20")
      (value "1k")
      (footprint "eagle-import:R0603")
      (libsource (lib "eagle-import") (part "R-US_R0603"))
    )
    (comp (ref "R21")
      (value "1k")
      (footprint "eagle-import:R0603")
      (libsource (lib "eagle-import") (part "R-US_R0603"))
    )
    (comp (ref "R22")
      (value "1k")
      (footprint "eagle-import:R0603")
      (libsource (lib "eagle-import") (part "R-US_R0603"))
    )
    (comp (ref "R23")
      (value "20k")
      (footprint "eagle-import:R0603")
      (libsource (lib "eagle-import") (part "R-US_R0603"))
    )
    (comp (ref "R24")
      (value "120k")
      (footprint "eagle-import:R0603")
      (libsource (lib "eagle-import") (part "R-US_R0603"))
    )
    (comp (ref "R25")
      (value "20k")
      (footprint "eagle-import:R0603")
      (libsource (lib "eagle-import") (part "R-US_R0603"))
    )
    (comp (ref "R26")
      (value "120k")
      (footprint "eagle-import:R0603")
      (libsource (lib "eagle-import") (part "R-US_R0603"))
    )
    (comp (ref "R27")
      (value "120k")
      (footprint "eagle-import:R0603")
      (libsource (lib "eagle-import") (part "R-US_R0603"))
    )
    (comp (ref "R28")
      (value "120k")
      (footprint "eagle-import:R0603")
      (libsource (lib "eagle-import") (part "R-US_R0603"))
    )
    (comp (ref "R29")
      (value "20k")
      (footprint "eagle-import:R0603")
      (libsource (lib "eagle-import") (part "R-US_R0603"))
    )
    (comp (ref "R30")
      (value "120k")
      (footprint "eagle-import:R0603")
      (libsource (lib "eagle-import") (part "R-US_R0603"))
    )
    (comp (ref "R31")
      (value "120k")
      (footprint "eagle-import:R0603")
      (libsource (lib "eagle-import") (part "R-US_R0603"))
    )
    (comp (ref "U$1")
      (value "MCP6004")
      (footprint "eagle-import:SO14")
      (libsource (lib "eagle-import") (part "MCP6004"))
    )
  )
  (nets
    (net (code "1") (name "+5V") (class "Default")
      (node (ref "C33") (pin "1") (pinfunction "1_1") (pintype "passive"))
      (node (ref "C36") (pin "1") (pinfunction "1_1") (pintype "passive"))
      (node (ref "C56") (pin "1") (pinfunction "1_1") (pintype "passive"))
      (node (ref "IC3") (pin "14") (pinfunction "VCC_14") (pintype "power_in"))
      (node (ref "U$4") (pin "4") (pinfunction "AVDD_4") (pintype "bidirectional"))
      (node (ref "U$6") (pin "1") (pinfunction "VOUT_1") (pintype "bidirectional"))
    )
    (net (code "2") (name "+12V") (class "Default")
      (node (ref "C22") (pin "1") (pinfunction "1_1") (pintype "passive"))
      (node (ref "C28") (pin "2") (pinfunction "2_2") (pintype "passive"))
      (node (ref "C30") (pin "2") (pinfunction "2_2") (pintype "passive"))
      (node (ref "C34") (pin "1") (pinfunction "1_1") (pintype "passive"))
      (node (ref "C39") (pin "1") (pinfunction "1_1") (pintype "passive"))
      (node (ref "C51") (pin "1") (pinfunction "1_1") (pintype "passive"))
      (node (ref "C53") (pin "1") (pinfunction "1_1") (pintype "passive"))
      (node (ref "IC1") (pin "4") (pinfunction "V+_4") (pintype "power_in"))
      (node (ref "IC2") (pin "8") (pinfunction "V+_8") (pintype "power_in"))
      (node (ref "IC4") (pin "8") (pinfunction "V+_8") (pintype "power_in"))
      (node (ref "IC5") (pin "8") (pinfunction "V+_8") (pintype "power_in"))
      (node (ref "L2") (pin "2") (pinfunction "2_2") (pintype "passive"))
      (node (ref "L4") (pin "1") (pinfunction "1_1") (pintype "passive"))
      (node (ref "L5") (pin "2") (pinfunction "2_2") (pintype "passive"))
      (node (ref "L7") (pin "1") (pinfunction "1_1") (pintype "passive"))
      (node (ref "U$5") (pin "3") (pinfunction "VIN_3") (pintype "bidirectional"))
    )
    (net (code "3") (name "-12V") (class "Default")
      (node (ref "C23") (pin "2") (pinfunction "2_2") (pintype "passive"))
      (node (ref "C27") (pin "1") (pinfunction "1_1") (pintype "passive"))
      (node (ref "C31") (pin "1") (pinfunction "1_1") (pintype "passive"))
      (node (ref "C38") (pin "2") (pinfunction "2_2") (pintype "passive"))
      (node (ref "C52") (pin "2") (pinfunction "2_2") (pintype "passive"))
      (node (ref "C54") (pin "2") (pinfunction "2_2") (pintype "passive"))
      (node (ref "IC1") (pin "11") (pinfunction "V-_11") (pintype "power_in"))
      (node (ref "IC2") (pin "4") (pinfunction "V-_4") (pintype "power_in"))
      (node (ref "IC4") (pin "4") (pinfunction "V-_4") (pintype "power_in"))
      (node (ref "IC5") (pin "4") (pinfunction "V-_4") (pintype "power_in"))
      (node (ref "L3") (pin "2") (pinfunction "2_2") (pintype "passive"))
      (node (ref "L6") (pin "2") (pinfunction "2_2") (pintype "passive"))
      (node (ref "R33") (pin "2") (pinfunction "2_2") (pintype "passive"))
    )
    (net (code "4") (name "ENC_A") (class "Default")
      (node (ref "SW1") (pin "B") (pinfunction "B_B") (pintype "passive"))
      (node (ref "U1") (pin "32") (pinfunction "PA11_32") (pintype "bidirectional"))
    )
    (net (code "5") (name "ENC_B") (class "Default")
      (node (ref "SW1") (pin "A") (pinfunction "A_A") (pintype "passive"))
      (node (ref "U1") (pin "33") (pinfunction "PA12_33") (pintype "bidirectional"))
    )
    (net (code "6") (name "ENC_SW") (class "Default")
      (node (ref "SW1") (pin "P1") (pinfunction "1_P1") (pintype "passive"))
      (node (ref "U1") (pin "22") (pinfunction "PE9_22") (pintype "bidirectional"))
    )
    (net (code "7") (name "GATE_1") (class "Default")
      (node (ref "IC3") (pin "2") (pinfunction "I_2") (pintype "input"))
      (node (ref "U3") (pin "13") (pinfunction "PA3_13") (pintype "bidirectional"))
    )
    (net (code "8") (name "GATE_2") (class "Default")
      (node (ref "IC3") (pin "5") (pinfunction "I_5") (pintype "input"))
      (node (ref "U3") (pin "15") (pinfunction "PA5_15") (pintype "bidirectional"))
    )
    (net (code "9") (name "GATE_3") (class "Default")
      (node (ref "IC3") (pin "9") (pinfunction "I_9") (pintype "input"))
      (node (ref "U3") (pin "12") (pinfunction "PA2_12") (pintype "bidirectional"))
    )
    (net (code "10") (name "GATE_4") (class "Default")
      (node (ref "IC3") (pin "12") (pinfunction "I_12") (pintype "input"))
      (node (ref "U3") (pin "11") (pinfunction "PA1_11") (pintype "bidirectional"))
    )
    (net (code "11") (name "GLED_1") (class "Default")
      (node (ref "R4") (pin "2") (pinfunction "2_2") (pintype "passive"))
      (node (ref "U1") (pin "30") (pinfunction "PA9_30") (pintype "bidirectional"))
    )
    (net (code "12") (name "GLED_2") (class "Default")
      (node (ref "R6") (pin "2") (pinfunction "2_2") (pintype "passive"))
      (node (ref "U1") (pin "11") (pinfunction "PA1_11") (pintype "bidirectional"))
    )
    (net (code "13") (name "GND") (class "Default")
      (node (ref "C10") (pin "1") (pinfunction "1_1") (pintype "passive"))
      (node (ref "C11") (pin "1") (pinfunction "1_1") (pintype "passive"))
      (node (ref "C12") (pin "1") (pinfunction "1_1") (pintype "passive"))
      (node (ref "C13") (pin "1") (pinfunction "1_1") (pintype "passive"))
      (node (ref "C14") (pin "1") (pinfunction "1_1") (pintype "passive"))
      (node (ref "C15") (pin "1") (pinfunction "1_1") (pintype "passive"))
      (node (ref "C16") (pin "2") (pinfunction "2_2") (pintype "passive"))
      (node (ref "C17") (pin "2") (pinfunction "2_2") (pintype "passive"))
      (node (ref "C18") (pin "1") (pinfunction "1_1") (pintype "passive"))
      (node (ref "C19") (pin "2") (pinfunction "2_2") (pintype "passive"))
      (node (ref "C20") (pin "2") (pinfunction "2_2") (pintype "passive"))
      (node (ref "C21") (pin "2") (pinfunction "2_2") (pintype "passive"))
      (node (ref "C22") (pin "2") (pinfunction "2_2") (pintype "passive"))
      (node (ref "C23") (pin "1") (pinfunction "1_1") (pintype "passive"))
      (node (ref "C24") (pin "1") (pinfunction "1_1") (pintype "passive"))
      (node (ref "C25") (pin "1") (pinfunction "1_1") (pintype "passive"))
      (node (ref "C26") (pin "1") (pinfunction "1_1") (pintype "passive"))
      (node (ref "C27") (pin "2") (pinfunction "2_2") (pintype "passive"))
      (node (ref "C28") (pin "1") (pinfunction "1_1") (pintype "passive"))
      (node (ref "C29") (pin "1") (pinfunction "1_1") (pintype "passive"))
      (node (ref "C30") (pin "1") (pinfunction "1_1") (pintype "passive"))
      (node (ref "C31") (pin "2") (pinfunction "2_2") (pintype "passive"))
      (node (ref "C32") (pin "1") (pinfunction "1_1") (pintype "passive"))
      (node (ref "C33") (pin "2") (pinfunction "2_2") (pintype "passive"))
      (node (ref "C34") (pin "2") (pinfunction "2_2") (pintype "passive"))
      (node (ref "C35") (pin "2") (pinfunction "2_2") (pintype "passive"))
      (node (ref "C36") (pin "2") (pinfunction "2_2") (pintype "passive"))
      (node (ref "C37") (pin "2") (pinfunction "2_2") (pintype "passive"))
      (node (ref "C38") (pin "1") (pinfunction "1_1") (pintype "passive"))
      (node (ref "C39") (pin "2") (pinfunction "2_2") (pintype "passive"))
      (node (ref "C40") (pin "2") (pinfunction "2_2") (pintype "passive"))
      (node (ref "C41") (pin "2") (pinfunction "2_2") (pintype "passive"))
      (node (ref "C42") (pin "2") (pinfunction "2_2") (pintype "passive"))
      (node (ref "C47") (pin "2") (pinfunction "2_2") (pintype "passive"))
      (node (ref "C48") (pin "2") (pinfunction "2_2") (pintype "passive"))
      (node (ref "C49") (pin "2") (pinfunction "2_2") (pintype "passive"))
      (node (ref "C50") (pin "2") (pinfunction "2_2") (pintype "passive"))
      (node (ref "C51") (pin "2") (pinfunction "2_2") (pintype "passive"))
      (node (ref "C52") (pin "1") (pinfunction "1_1") (pintype "passive"))
      (node (ref "C53") (pin "2") (pinfunction "2_2") (pintype "passive"))
      (node (ref "C54") (pin "1") (pinfunction "1_1") (pintype "passive"))
      (node (ref "C55") (pin "2") (pinfunction "2_2") (pintype "passive"))
      (node (ref "C56") (pin "2") (pinfunction "2_2") (pintype "passive"))
      (node (ref "C57") (pin "2") (pinfunction "2_2") (pintype "passive"))
      (node (ref "C7") (pin "2") (pinfunction "2_2") (pintype "passive"))
      (node (ref "C8") (pin "1") (pinfunction "1_1") (pintype "passive"))
      (node (ref "C9") (pin "1") (pinfunction "1_1") (pintype "passive"))
      (node (ref "IC1") (pin "10") (pinfunction "+IN_10") (pintype "input"))
      (node (ref "IC1") (pin "12") (pinfunction "+IN_12") (pintype "input"))
      (node (ref "IC1") (pin "3") (pinfunction "+IN_3") (pintype "input"))
      (node (ref "IC1") (pin "5") (pinfunction "+IN_5") (pintype "input"))
      (node (ref "IC2") (pin "3") (pinfunction "+IN_3") (pintype "input"))
      (node (ref "IC2") (pin "5") (pinfunction "+IN_5") (pintype "input"))
      (node (ref "IC3") (pin "1") (pinfunction "OE_1") (pintype "input"))
      (node (ref "IC3") (pin "10") (pinfunction "OE_10") (pintype "input"))
      (node (ref "IC3") (pin "13") (pinfunction "OE_13") (pintype "input"))
      (node (ref "IC3") (pin "4") (pinfunction "OE_4") (pintype "input"))
      (node (ref "IC3") (pin "7") (pinfunction "GND_7") (pintype "power_in"))
      (node (ref "J1") (pin "4") (pinfunction "GND_4") (pintype "bidirectional"))
      (node (ref "J1") (pin "SHELL") (pinfunction "SHIELD_SHELL") (pintype "bidirectional"))
      (node (ref "J1") (pin "SHELL1") (pinfunction "SHIELD_SHELL1") (pintype "bidirectional"))
      (node (ref "J2") (pin "3") (pinfunction "3_3") (pintype "passive"))
      (node (ref "J2") (pin "4") (pinfunction "4_4") (pintype "passive"))
      (node (ref "J2") (pin "5") (pinfunction "5_5") (pintype "passive"))
      (node (ref "J2") (pin "6") (pinfunction "6_6") (pintype "passive"))
      (node (ref "J2") (pin "7") (pinfunction "7_7") (pintype "passive"))
      (node (ref "J2") (pin "8") (pinfunction "8_8") (pintype "passive"))
      (node (ref "JCK1") (pin "P$3_SLEEVE") (pinfunction "SLEEVE_P$3_SLEEVE") (pintype "passive"))
      (node (ref "JCK10") (pin "P$3_SLEEVE") (pinfunction "SLEEVE_P$3_SLEEVE") (pintype "passive"))
      (node (ref "JCK11") (pin "P$3_SLEEVE") (pinfunction "SLEEVE_P$3_SLEEVE") (pintype "passive"))
      (node (ref "JCK12") (pin "P$3_SLEEVE") (pinfunction "SLEEVE_P$3_SLEEVE") (pintype "passive"))
      (node (ref "JCK13") (pin "P$3_SLEEVE") (pinfunction "SLEEVE_P$3_SLEEVE") (pintype "passive"))
      (node (ref "JCK14") (pin "P$3_SLEEVE") (pinfunction "SLEEVE_P$3_SLEEVE") (pintype "passive"))
      (node (ref "JCK2") (pin "P$3_SLEEVE") (pinfunction "SLEEVE_P$3_SLEEVE") (pintype "passive"))
      (node (ref "JCK3") (pin "P$3_SLEEVE") (pinfunction "SLEEVE_P$3_SLEEVE") (pintype "passive"))
      (node (ref "JCK4") (pin "P$3_SLEEVE") (pinfunction "SLEEVE_P$3_SLEEVE") (pintype "passive"))
      (node (ref "JCK5") (pin "P$3_SLEEVE") (pinfunction "SLEEVE_P$3_SLEEVE") (pintype "passive"))
      (node (ref "JCK6") (pin "P$3_SLEEVE") (pinfunction "SLEEVE_P$3_SLEEVE") (pintype "passive"))
      (node (ref "JCK7") (pin "P$3_SLEEVE") (pinfunction "SLEEVE_P$3_SLEEVE") (pintype "passive"))
      (node (ref "JCK8") (pin "P$3_SLEEVE") (pinfunction "SLEEVE_P$3_SLEEVE") (pintype "passive"))
      (node (ref "JCK9") (pin "P$3_SLEEVE") (pinfunction "SLEEVE_P$3_SLEEVE") (pintype "passive"))
      (node (ref "LED1") (pin "K") (pinfunction "C_K") (pintype "passive"))
      (node (ref "LED2") (pin "K") (pinfunction "C_K") (pintype "passive"))
      (node (ref "LED3") (pin "K") (pinfunction "C_K") (pintype "passive"))
      (node (ref "LED4") (pin "2") (pinfunction "A_2") (pintype "passive"))
      (node (ref "LED5") (pin "2") (pinfunction "A_2") (pintype "passive"))
      (node (ref "LED6") (pin "2") (pinfunction "A_2") (pintype "passive"))
      (node (ref "LED7") (pin "2") (pinfunction "A_2") (pintype "passive"))
      (node (ref "LED8") (pin "2") (pinfunction "A_2") (pintype "passive"))
      (node (ref "LED9") (pin "2") (pinfunction "A_2") (pintype "passive"))
      (node (ref "Q1") (pin "2") (pinfunction "2_2") (pintype "passive"))
      (node (ref "Q1") (pin "4") (pinfunction "4_4") (pintype "passive"))
      (node (ref "Q2") (pin "2") (pinfunction "2_2") (pintype "passive"))
      (node (ref "Q2") (pin "4") (pinfunction "4_4") (pintype "passive"))
      (node (ref "R52") (pin "1") (pinfunction "1_1") (pintype "passive"))
      (node (ref "S1") (pin "P$3") (pinfunction "3_P$3") (pintype "bidirectional"))
      (node (ref "S1") (pin "P$4") (pinfunction "4_P$4") (pintype "bidirectional"))
      (node (ref "S2") (pin "P$3") (pinfunction "3_P$3") (pintype "bidirectional"))
      (node (ref "S2") (pin "P$4") (pinfunction "4_P$4") (pintype "bidirectional"))
      (node (ref "S3") (pin "P$1") (pinfunction "1_P$1") (pintype "bidirectional"))
      (node (ref "S3") (pin "P$2") (pinfunction "2_P$2") (pintype "bidirectional"))
      (node (ref "SV1") (pin "3") (pinfunction "3_3") (pintype "passive"))
      (node (ref "SV1") (pin "4") (pinfunction "4_4") (pintype "passive"))
      (node (ref "SV1") (pin "5") (pinfunction "5_5") (pintype "passive"))
      (node (ref "SV1") (pin "6") (pinfunction "6_6") (pintype "passive"))
      (node (ref "SV1") (pin "7") (pinfunction "7_7") (pintype "passive"))
      (node (ref "SV1") (pin "8") (pinfunction "8_8") (pintype "passive"))
      (node (ref "SV2") (pin "1") (pinfunction "1_1") (pintype "passive"))
      (node (ref "SW1") (pin "C") (pinfunction "C_C") (pintype "passive"))
      (node (ref "SW1") (pin "GND@1") (pinfunction "P$1_GND@1") (pintype "bidirectional"))
      (node (ref "SW1") (pin "GND@2") (pinfunction "P$2_GND@2") (pintype "bidirectional"))
      (node (ref "SW1") (pin "P2") (pinfunction "2_P2") (pintype "passive"))
      (node (ref "SWD_CON") (pin "4") (pinfunction "4_4") (pintype "passive"))
      (node (ref "U$1") (pin "10") (pinfunction "+IN_10") (pintype "input"))
      (node (ref "U$1") (pin "11") (pinfunction "V-_11") (pintype "power_in"))
      (node (ref "U$1") (pin "12") (pinfunction "+IN_12") (pintype "input"))
      (node (ref "U$1") (pin "3") (pinfunction "+IN_3") (pintype "input"))
      (node (ref "U$1") (pin "5") (pinfunction "+IN_5") (pintype "input"))
      (node (ref "U$2") (pin "1") (pinfunction "GND_1") (pintype "power_in"))
      (node (ref "U$3") (pin "2") (pinfunction "GND_2") (pintype "bidirectional"))
      (node (ref "U$3") (pin "2@1") (pinfunction "GND_2@1") (pintype "bidirectional"))
      (node (ref "U$4") (pin "14") (pinfunction "RSTSEL_14") (pintype "bidirectional"))
      (node (ref "U$4") (pin "15") (pinfunction "__ENABLE_15") (pintype "bidirectional"))
      (node (ref "U$4") (pin "5") (pinfunction "VREFL_5") (pintype "bidirectional"))
      (node (ref "U$4") (pin "6") (pinfunction "GND_6") (pintype "bidirectional"))
      (node (ref "U$5") (pin "2") (pinfunction "GND_2") (pintype "bidirectional"))
      (node (ref "U$5") (pin "2@1") (pinfunction "GND_2@1") (pintype "bidirectional"))
      (node (ref "U$6") (pin "2") (pinfunction "GND_2") (pintype "bidirectional"))
      (node (ref "U$6") (pin "2@1") (pinfunction "GND_2@1") (pintype "bidirectional"))
      (node (ref "U1") (pin "23") (pinfunction "VSSSD_23") (pintype "bidirectional"))
      (node (ref "U1") (pin "44") (pinfunction "BOOT0_44") (pintype "bidirectional"))
      (node (ref "U1") (pin "47") (pinfunction "VSS_47") (pintype "bidirectional"))
      (node (ref "U1") (pin "8") (pinfunction "VSSA_8") (pintype "bidirectional"))
      (node (ref "U2") (pin "1") (pinfunction "C_1") (pintype "passive"))
      (node (ref "U3") (pin "23") (pinfunction "VSSSD_23") (pintype "bidirectional"))
      (node (ref "U3") (pin "44") (pinfunction "BOOT0_44") (pintype "bidirectional"))
      (node (ref "U3") (pin "47") (pinfunction "VSS_47") (pintype "bidirectional"))
      (node (ref "U3") (pin "8") (pinfunction "VSSA_8") (pintype "bidirectional"))
      (node (ref "U5") (pin "2") (pinfunction "GND_2") (pintype "bidirectional"))
    )
    (net (code "14") (name "L1G") (class "Default")
      (node (ref "R54") (pin "2") (pinfunction "2_2") (pintype "passive"))
      (node (ref "U3") (pin "14") (pinfunction "PA4_14") (pintype "bidirectional"))
    )
    (net (code "15") (name "L1R") (class "Default")
      (node (ref "R53") (pin "2") (pinfunction "2_2") (pintype "passive"))
      (node (ref "U3") (pin "16") (pinfunction "PA6_16") (pintype "bidirectional"))
    )
    (net (code "16") (name "L2G") (class "Default")
      (node (ref "R56") (pin "2") (pinfunction "2_2") (pintype "passive"))
      (node (ref "U3") (pin "18") (pinfunction "PB0_18") (pintype "bidirectional"))
    )
    (net (code "17") (name "L2R") (class "Default")
      (node (ref "R55") (pin "2") (pinfunction "2_2") (pintype "passive"))
      (node (ref "U3") (pin "19") (pinfunction "PB1_19") (pintype "bidirectional"))
    )
    (net (code "18") (name "L3G") (class "Default")
      (node (ref "R58") (pin "2") (pinfunction "2_2") (pintype "passive"))
      (node (ref "U3") (pin "46") (pinfunction "PB9_46") (pintype "bidirectional"))
    )
    (net (code "19") (name "L3R") (class "Default")
      (node (ref "R57") (pin "2") (pinfunction "2_2") (pintype "passive"))
      (node (ref "U3") (pin "45") (pinfunction "PB8_45") (pintype "bidirectional"))
    )
    (net (code "20") (name "L4G") (class "Default")
      (node (ref "R60") (pin "2") (pinfunction "2_2") (pintype "passive"))
      (node (ref "U3") (pin "43") (pinfunction "PB7_43") (pintype "bidirectional"))
    )
    (net (code "21") (name "L4R") (class "Default")
      (node (ref "R59") (pin "2") (pinfunction "2_2") (pintype "passive"))
      (node (ref "U3") (pin "42") (pinfunction "PB6_42") (pintype "bidirectional"))
    )
    (net (code "22") (name "LED_1") (class "Default")
      (node (ref "R1") (pin "2") (pinfunction "2_2") (pintype "passive"))
      (node (ref "U1") (pin "19") (pinfunction "PB1_19") (pintype "bidirectional"))
    )
    (net (code "23") (name "LED_2") (class "Default")
      (node (ref "R2") (pin "2") (pinfunction "2_2") (pintype "passive"))
      (node (ref "U1") (pin "16") (pinfunction "PA6_16") (pintype "bidirectional"))
    )
    (net (code "24") (name "LED_3") (class "Default")
      (node (ref "R3") (pin "2") (pinfunction "2_2") (pintype "passive"))
      (node (ref "U1") (pin "14") (pinfunction "PA4_14") (pintype "bidirectional"))
    )
    (net (code "25") (name "Net-(C21-Pad1)") (class "Default")
      (node (ref "C21") (pin "1") (pinfunction "1_1") (pintype "passive"))
      (node (ref "D1") (pin "C") (pinfunction "C_C") (pintype "passive"))
      (node (ref "L1") (pin "1") (pinfunction "1_1") (pintype "passive"))
      (node (ref "L2") (pin "1") (pinfunction "1_1") (pintype "passive"))
    )
    (net (code "26") (name "Net-(D1-PadA)") (class "Default")
      (node (ref "D1") (pin "A") (pinfunction "A_A") (pintype "passive"))
      (node (ref "J2") (pin "10") (pinfunction "10_10") (pintype "passive"))
      (node (ref "J2") (pin "9") (pinfunction "9_9") (pintype "passive"))
    )
    (net (code "27") (name "Net-(D2-PadA)") (class "Default")
      (node (ref "D2") (pin "A") (pinfunction "A_A") (pintype "passive"))
      (node (ref "L3") (pin "1") (pinfunction "1_1") (pintype "passive"))
    )
    (net (code "28") (name "Net-(D2-PadC)") (class "Default")
      (node (ref "D2") (pin "C") (pinfunction "C_C") (pintype "passive"))
      (node (ref "J2") (pin "1") (pinfunction "1_1") (pintype "passive"))
      (node (ref "J2") (pin "2") (pinfunction "2_2") (pintype "passive"))
    )
    (net (code "29") (name "Net-(D3-PadA)") (class "Default")
      (node (ref "D3") (pin "A") (pinfunction "A_A") (pintype "passive"))
      (node (ref "SV1") (pin "10") (pinfunction "10_10") (pintype "passive"))
      (node (ref "SV1") (pin "9") (pinfunction "9_9") (pintype "passive"))
    )
    (net (code "30") (name "Net-(D3-PadC)") (class "Default")
      (node (ref "D3") (pin "C") (pinfunction "C_C") (pintype "passive"))
      (node (ref "L5") (pin "1") (pinfunction "1_1") (pintype "passive"))
    )
    (net (code "31") (name "Net-(D4-PadA)") (class "Default")
      (node (ref "D4") (pin "A") (pinfunction "A_A") (pintype "passive"))
      (node (ref "L6") (pin "1") (pinfunction "1_1") (pintype "passive"))
    )
    (net (code "32") (name "Net-(D4-PadC)") (class "Default")
      (node (ref "D4") (pin "C") (pinfunction "C_C") (pintype "passive"))
      (node (ref "SV1") (pin "1") (pinfunction "1_1") (pintype "passive"))
      (node (ref "SV1") (pin "2") (pinfunction "2_2") (pintype "passive"))
    )
    (net (code "33") (name "Net-(IC1A--IN)") (class "Default")
      (node (ref "C6") (pin "1") (pinfunction "1_1") (pintype "passive"))
      (node (ref "IC1") (pin "2") (pinfunction "-IN_2") (pintype "input"))
      (node (ref "R18") (pin "1") (pinfunction "1_1") (pintype "passive"))
      (node (ref "R19") (pin "2") (pinfunction "2_2") (pintype "passive"))
    )
    (net (code "34") (name "Net-(IC1A-OUT)") (class "Default")
      (node (ref "C6") (pin "2") (pinfunction "2_2") (pintype "passive"))
      (node (ref "IC1") (pin "1") (pinfunction "OUT_1") (pintype "output"))
      (node (ref "R18") (pin "2") (pinfunction "2_2") (pintype "passive"))
      (node (ref "R22") (pin "1") (pinfunction "1_1") (pintype "passive"))
    )
    (net (code "35") (name "Net-(IC1B--IN)") (class "Default")
      (node (ref "IC1") (pin "6") (pinfunction "-IN_6") (pintype "input"))
      (node (ref "R12") (pin "1") (pinfunction "1_1") (pintype "passive"))
      (node (ref "R13") (pin "2") (pinfunction "2_2") (pintype "passive"))
    )
    (net (code "36") (name "Net-(IC1B-OUT)") (class "Default")
      (node (ref "IC1") (pin "7") (pinfunction "OUT_7") (pintype "output"))
      (node (ref "R12") (pin "2") (pinfunction "2_2") (pintype "passive"))
      (node (ref "R19") (pin "1") (pinfunction "1_1") (pintype "passive"))
      (node (ref "R30") (pin "1") (pinfunction "1_1") (pintype "passive"))
    )
    (net (code "37") (name "Net-(IC1C--IN)") (class "Default")
      (node (ref "IC1") (pin "9") (pinfunction "-IN_9") (pintype "input"))
      (node (ref "R8") (pin "1") (pinfunction "1_1") (pintype "passive"))
      (node (ref "R9") (pin "2") (pinfunction "2_2") (pintype "passive"))
    )
    (net (code "38") (name "Net-(IC1C-OUT)") (class "Default")
      (node (ref "IC1") (pin "8") (pinfunction "OUT_8") (pintype "output"))
      (node (ref "R15") (pin "1") (pinfunction "1_1") (pintype "passive"))
      (node (ref "R24") (pin "1") (pinfunction "1_1") (pintype "passive"))
      (node (ref "R8") (pin "2") (pinfunction "2_2") (pintype "passive"))
    )
    (net (code "39") (name "Net-(IC1D--IN)") (class "Default")
      (node (ref "IC1") (pin "13") (pinfunction "-IN_13") (pintype "input"))
      (node (ref "R10") (pin "1") (pinfunction "1_1") (pintype "passive"))
      (node (ref "R11") (pin "2") (pinfunction "2_2") (pintype "passive"))
    )
    (net (code "40") (name "Net-(IC1D-OUT)") (class "Default")
      (node (ref "IC1") (pin "14") (pinfunction "OUT_14") (pintype "output"))
      (node (ref "R10") (pin "2") (pinfunction "2_2") (pintype "passive"))
      (node (ref "R17") (pin "1") (pinfunction "1_1") (pintype "passive"))
      (node (ref "R27") (pin "1") (pinfunction "1_1") (pintype "passive"))
    )
    (net (code "41") (name "Net-(IC2A--IN)") (class "Default")
      (node (ref "C4") (pin "1") (pinfunction "1_1") (pintype "passive"))
      (node (ref "IC2") (pin "2") (pinfunction "-IN_2") (pintype "input"))
      (node (ref "R14") (pin "1") (pinfunction "1_1") (pintype "passive"))
      (node (ref "R15") (pin "2") (pinfunction "2_2") (pintype "passive"))
    )
    (net (code "42") (name "Net-(IC2A-OUT)") (class "Default")
      (node (ref "C4") (pin "2") (pinfunction "2_2") (pintype "passive"))
      (node (ref "IC2") (pin "1") (pinfunction "OUT_1") (pintype "output"))
      (node (ref "R14") (pin "2") (pinfunction "2_2") (pintype "passive"))
      (node (ref "R20") (pin "1") (pinfunction "1_1") (pintype "passive"))
    )
    (net (code "43") (name "Net-(IC2B--IN)") (class "Default")
      (node (ref "C5") (pin "1") (pinfunction "1_1") (pintype "passive"))
      (node (ref "IC2") (pin "6") (pinfunction "-IN_6") (pintype "input"))
      (node (ref "R16") (pin "1") (pinfunction "1_1") (pintype "passive"))
      (node (ref "R17") (pin "2") (pinfunction "2_2") (pintype "passive"))
    )
    (net (code "44") (name "Net-(IC2B-OUT)") (class "Default")
      (node (ref "C5") (pin "2") (pinfunction "2_2") (pintype "passive"))
      (node (ref "IC2") (pin "7") (pinfunction "OUT_7") (pintype "output"))
      (node (ref "R16") (pin "2") (pinfunction "2_2") (pintype "passive"))
      (node (ref "R21") (pin "1") (pinfunction "1_1") (pintype "passive"))
    )
    (net (code "45") (name "Net-(IC3A-O)") (class "Default")
      (node (ref "IC3") (pin "3") (pinfunction "O_3") (pintype "tri_state"))
      (node (ref "R34") (pin "1") (pinfunction "1_1") (pintype "passive"))
    )
    (net (code "46") (name "Net-(IC3B-O)") (class "Default")
      (node (ref "IC3") (pin "6") (pinfunction "O_6") (pintype "tri_state"))
      (node (ref "R35") (pin "1") (pinfunction "1_1") (pintype "passive"))
    )
    (net (code "47") (name "Net-(IC3C-O)") (class "Default")
      (node (ref "IC3") (pin "8") (pinfunction "O_8") (pintype "tri_state"))
      (node (ref "R36") (pin "1") (pinfunction "1_1") (pintype "passive"))
    )
    (net (code "48") (name "Net-(IC3D-O)") (class "Default")
      (node (ref "IC3") (pin "11") (pinfunction "O_11") (pintype "tri_state"))
      (node (ref "R37") (pin "1") (pinfunction "1_1") (pintype "passive"))
    )
    (net (code "49") (name "Net-(IC4A--IN)") (class "Default")
      (node (ref "C43") (pin "2") (pinfunction "2_2") (pintype "passive"))
      (node (ref "IC4") (pin "2") (pinfunction "-IN_2") (pintype "input"))
      (node (ref "R38") (pin "1") (pinfunction "1_1") (pintype "passive"))
      (node (ref "R40") (pin "2") (pinfunction "2_2") (pintype "passive"))
    )
    (net (code "50") (name "Net-(IC4A-OUT)") (class "Default")
      (node (ref "C43") (pin "1") (pinfunction "1_1") (pintype "passive"))
      (node (ref "IC4") (pin "1") (pinfunction "OUT_1") (pintype "output"))
      (node (ref "R39") (pin "1") (pinfunction "1_1") (pintype "passive"))
    )
    (net (code "51") (name "Net-(IC4B--IN)") (class "Default")
      (node (ref "C44") (pin "2") (pinfunction "2_2") (pintype "passive"))
      (node (ref "IC4") (pin "6") (pinfunction "-IN_6") (pintype "input"))
      (node (ref "R41") (pin "1") (pinfunction "1_1") (pintype "passive"))
      (node (ref "R43") (pin "2") (pinfunction "2_2") (pintype "passive"))
    )
    (net (code "52") (name "Net-(IC4B-OUT)") (class "Default")
      (node (ref "C44") (pin "1") (pinfunction "1_1") (pintype "passive"))
      (node (ref "IC4") (pin "7") (pinfunction "OUT_7") (pintype "output"))
      (node (ref "R42") (pin "1") (pinfunction "1_1") (pintype "passive"))
    )
    (net (code "53") (name "Net-(IC5A--IN)") (class "Default")
      (node (ref "C45") (pin "2") (pinfunction "2_2") (pintype "passive"))
      (node (ref "IC5") (pin "2") (pinfunction "-IN_2") (pintype "input"))
      (node (ref "R44") (pin "1") (pinfunction "1_1") (pintype "passive"))
      (node (ref "R46") (pin "2") (pinfunction "2_2") (pintype "passive"))
    )
    (net (code "54") (name "Net-(IC5A-OUT)") (class "Default")
      (node (ref "C45") (pin "1") (pinfunction "1_1") (pintype "passive"))
      (node (ref "IC5") (pin "1") (pinfunction "OUT_1") (pintype "output"))
      (node (ref "R45") (pin "1") (pinfunction "1_1") (pintype "passive"))
    )
    (net (code "55") (name "Net-(IC5B--IN)") (class "Default")
      (node (ref "C46") (pin "2") (pinfunction "2_2") (pintype "passive"))
      (node (ref "IC5") (pin "6") (pinfunction "-IN_6") (pintype "input"))
      (node (ref "R47") (pin "1") (pinfunction "1_1") (pintype "passive"))
      (node (ref "R49") (pin "2") (pinfunction "2_2") (pintype "passive"))
    )
    (net (code "56") (name "Net-(IC5B-OUT)") (class "Default")
      (node (ref "C46") (pin "1") (pinfunction "1_1") (pintype "passive"))
      (node (ref "IC5") (pin "7") (pinfunction "OUT_7") (pintype "output"))
      (node (ref "R48") (pin "1") (pinfunction "1_1") (pintype "passive"))
    )
    (net (code "57") (name "Net-(JCK1-TIP)") (class "Default")
      (node (ref "JCK1") (pin "P$1_TIP") (pinfunction "TIP_P$1_TIP") (pintype "passive"))
      (node (ref "R9") (pin "1") (pinfunction "1_1") (pintype "passive"))
    )
    (net (code "58") (name "Net-(JCK2-TIP)") (class "Default")
      (node (ref "JCK2") (pin "P$1_TIP") (pinfunction "TIP_P$1_TIP") (pintype "passive"))
      (node (ref "R11") (pin "1") (pinfunction "1_1") (pintype "passive"))
    )
    (net (code "59") (name "Net-(JCK3-TIP)") (class "Default")
      (node (ref "JCK3") (pin "P$1_TIP") (pinfunction "TIP_P$1_TIP") (pintype "passive"))
      (node (ref "R13") (pin "1") (pinfunction "1_1") (pintype "passive"))
    )
    (net (code "60") (name "Net-(JCK4-TIP)") (class "Default")
      (node (ref "JCK4") (pin "P$1_TIP") (pinfunction "TIP_P$1_TIP") (pintype "passive"))
      (node (ref "R20") (pin "2") (pinfunction "2_2") (pintype "passive"))
    )
    (net (code "61") (name "Net-(JCK5-TIP)") (class "Default")
      (node (ref "JCK5") (pin "P$1_TIP") (pinfunction "TIP_P$1_TIP") (pintype "passive"))
      (node (ref "R21") (pin "2") (pinfunction "2_2") (pintype "passive"))
    )
    (net (code "62") (name "Net-(JCK6-TIP)") (class "Default")
      (node (ref "JCK6") (pin "P$1_TIP") (pinfunction "TIP_P$1_TIP") (pintype "passive"))
      (node (ref "R22") (pin "2") (pinfunction "2_2") (pintype "passive"))
    )
    (net (code "63") (name "Net-(JCK7-TIP)") (class "Default")
      (node (ref "JCK7") (pin "P$1_TIP") (pinfunction "TIP_P$1_TIP") (pintype "passive"))
      (node (ref "R38") (pin "2") (pinfunction "2_2") (pintype "passive"))
      (node (ref "R39") (pin "2") (pinfunction "2_2") (pintype "passive"))
    )
    (net (code "64") (name "Net-(JCK8-TIP)") (class "Default")
      (node (ref "JCK8") (pin "P$1_TIP") (pinfunction "TIP_P$1_TIP") (pintype "passive"))
      (node (ref "R41") (pin "2") (pinfunction "2_2") (pintype "passive"))
      (node (ref "R42") (pin "2") (pinfunction "2_2") (pintype "passive"))
    )
    (net (code "65") (name "Net-(JCK9-TIP)") (class "Default")
      (node (ref "JCK9") (pin "P$1_TIP") (pinfunction "TIP_P$1_TIP") (pintype "passive"))
      (node (ref "R44") (pin "2") (pinfunction "2_2") (pintype "passive"))
      (node (ref "R45") (pin "2") (pinfunction "2_2") (pintype "passive"))
    )
    (net (code "66") (name "Net-(JCK10-TIP)") (class "Default")
      (node (ref "JCK10") (pin "P$1_TIP") (pinfunction "TIP_P$1_TIP") (pintype "passive"))
      (node (ref "R47") (pin "2") (pinfunction "2_2") (pintype "passive"))
      (node (ref "R48") (pin "2") (pinfunction "2_2") (pintype "passive"))
    )
    (net (code "67") (name "Net-(JCK11-TIP)") (class "Default")
      (node (ref "JCK11") (pin "P$1_TIP") (pinfunction "TIP_P$1_TIP") (pintype "passive"))
      (node (ref "R34") (pin "2") (pinfunction "2_2") (pintype "passive"))
    )
    (net (code "68") (name "Net-(JCK12-TIP)") (class "Default")
      (node (ref "JCK12") (pin "P$1_TIP") (pinfunction "TIP_P$1_TIP") (pintype "passive"))
      (node (ref "R35") (pin "2") (pinfunction "2_2") (pintype "passive"))
    )
    (net (code "69") (name "Net-(JCK13-TIP)") (class "Default")
      (node (ref "JCK13") (pin "P$1_TIP") (pinfunction "TIP_P$1_TIP") (pintype "passive"))
      (node (ref "R36") (pin "2") (pinfunction "2_2") (pintype "passive"))
    )
    (net (code "70") (name "Net-(JCK14-TIP)") (class "Default")
      (node (ref "JCK14") (pin "P$1_TIP") (pinfunction "TIP_P$1_TIP") (pintype "passive"))
      (node (ref "R37") (pin "2") (pinfunction "2_2") (pintype "passive"))
    )
    (net (code "71") (name "Net-(LED1-PadA)") (class "Default")
      (node (ref "LED1") (pin "A") (pinfunction "A_A") (pintype "passive"))
      (node (ref "R1") (pin "1") (pinfunction "1_1") (pintype "passive"))
    )
    (net (code "72") (name "Net-(LED2-PadA)") (class "Default")
      (node (ref "LED2") (pin "A") (pinfunction "A_A") (pintype "passive"))
      (node (ref "R2") (pin "1") (pinfunction "1_1") (pintype "passive"))
    )
    (net (code "73") (name "Net-(LED3-PadA)") (class "Default")
      (node (ref "LED3") (pin "A") (pinfunction "A_A") (pintype "passive"))
      (node (ref "R3") (pin "1") (pinfunction "1_1") (pintype "passive"))
    )
    (net (code "74") (name "Net-(LED4-CG)") (class "Default")
      (node (ref "LED4") (pin "1") (pinfunction "CG_1") (pintype "passive"))
      (node (ref "R4") (pin "1") (pinfunction "1_1") (pintype "passive"))
    )
    (net (code "75") (name "Net-(LED4-CR)") (class "Default")
      (node (ref "LED4") (pin "3") (pinfunction "CR_3") (pintype "passive"))
      (node (ref "R5") (pin "1") (pinfunction "1_1") (pintype "passive"))
    )
    (net (code "76") (name "Net-(LED5-CG)") (class "Default")
      (node (ref "LED5") (pin "1") (pinfunction "CG_1") (pintype "passive"))
      (node (ref "R6") (pin "1") (pinfunction "1_1") (pintype "passive"))
    )
    (net (code "77") (name "Net-(LED5-CR)") (class "Default")
      (node (ref "LED5") (pin "3") (pinfunction "CR_3") (pintype "passive"))
      (node (ref "R7") (pin "1") (pinfunction "1_1") (pintype "passive"))
    )
    (net (code "78") (name "Net-(LED6-CG)") (class "Default")
      (node (ref "LED6") (pin "1") (pinfunction "CG_1") (pintype "passive"))
      (node (ref "R54") (pin "1") (pinfunction "1_1") (pintype "passive"))
    )
    (net (code "79") (name "Net-(LED6-CR)") (class "Default")
      (node (ref "LED6") (pin "3") (pinfunction "CR_3") (pintype "passive"))
      (node (ref "R53") (pin "1") (pinfunction "1_1") (pintype "passive"))
    )
    (net (code "80") (name "Net-(LED7-CG)") (class "Default")
      (node (ref "LED7") (pin "1") (pinfunction "CG_1") (pintype "passive"))
      (node (ref "R56") (pin "1") (pinfunction "1_1") (pintype "passive"))
    )
    (net (code "81") (name "Net-(LED7-CR)") (class "Default")
      (node (ref "LED7") (pin "3") (pinfunction "CR_3") (pintype "passive"))
      (node (ref "R55") (pin "1") (pinfunction "1_1") (pintype "passive"))
    )
    (net (code "82") (name "Net-(LED8-CG)") (class "Default")
      (node (ref "LED8") (pin "1") (pinfunction "CG_1") (pintype "passive"))
      (node (ref "R58") (pin "1") (pinfunction "1_1") (pintype "passive"))
    )
    (net (code "83") (name "Net-(LED8-CR)") (class "Default")
      (node (ref "LED8") (pin "3") (pinfunction "CR_3") (pintype "passive"))
      (node (ref "R57") (pin "1") (pinfunction "1_1") (pintype "passive"))
    )
    (net (code "84") (name "Net-(LED9-CG)") (class "Default")
      (node (ref "LED9") (pin "1") (pinfunction "CG_1") (pintype "passive"))
      (node (ref "R60") (pin "1") (pinfunction "1_1") (pintype "passive"))
    )
    (net (code "85") (name "Net-(LED9-CR)") (class "Default")
      (node (ref "LED9") (pin "3") (pinfunction "CR_3") (pintype "passive"))
      (node (ref "R59") (pin "1") (pinfunction "1_1") (pintype "passive"))
    )
    (net (code "86") (name "Net-(U$1A--IN)") (class "Default")
      (node (ref "U$1") (pin "1") (pinfunction "OUT_1") (pintype "output"))
      (node (ref "U$1") (pin "2") (pinfunction "-IN_2") (pintype "input"))
    )
    (net (code "87") (name "Net-(U$1B--IN)") (class "Default")
      (node (ref "C3") (pin "1") (pinfunction "1_1") (pintype "passive"))
      (node (ref "R29") (pin "1") (pinfunction "1_1") (pintype "passive"))
      (node (ref "R30") (pin "2") (pinfunction "2_2") (pintype "passive"))
      (node (ref "R31") (pin "2") (pinfunction "2_2") (pintype "passive"))
      (node (ref "U$1") (pin "6") (pinfunction "-IN_6") (pintype "input"))
    )
    (net (code "88") (name "Net-(U$1C--IN)") (class "Default")
      (node (ref "C2") (pin "1") (pinfunction "1_1") (pintype "passive"))
      (node (ref "R25") (pin "1") (pinfunction "1_1") (pintype "passive"))
      (node (ref "R27") (pin "2") (pinfunction "2_2") (pintype "passive"))
      (node (ref "R28") (pin "2") (pinfunction "2_2") (pintype "passive"))
      (node (ref "U$1") (pin "9") (pinfunction "-IN_9") (pintype "input"))
    )
    (net (code "89") (name "Net-(U$1D--IN)") (class "Default")
      (node (ref "C1") (pin "1") (pinfunction "1_1") (pintype "passive"))
      (node (ref "R23") (pin "1") (pinfunction "1_1") (pintype "passive"))
      (node (ref "R24") (pin "2") (pinfunction "2_2") (pintype "passive"))
      (node (ref "R26") (pin "2") (pinfunction "2_2") (pintype "passive"))
      (node (ref "U$1") (pin "13") (pinfunction "-IN_13") (pintype "input"))
    )
    (net (code "90") (name "Net-(U$3-VIN)") (class "Default")
      (node (ref "C17") (pin "1") (pinfunction "1_1") (pintype "passive"))
      (node (ref "L4") (pin "2") (pinfunction "2_2") (pintype "passive"))
      (node (ref "U$3") (pin "3") (pinfunction "VIN_3") (pintype "bidirectional"))
    )
    (net (code "91") (name "Net-(U$4-VREFH{slash}OUT)") (class "Default")
      (node (ref "C55") (pin "1") (pinfunction "1_1") (pintype "passive"))
      (node (ref "R51") (pin "2") (pinfunction "2_2") (pintype "passive"))
      (node (ref "U$4") (pin "3") (pinfunction "VREFH/OUT_3") (pintype "bidirectional"))
    )
    (net (code "92") (name "Net-(U$6-VIN)") (class "Default")
      (node (ref "C37") (pin "1") (pinfunction "1_1") (pintype "passive"))
      (node (ref "L7") (pin "2") (pinfunction "2_2") (pintype "passive"))
      (node (ref "U$6") (pin "3") (pinfunction "VIN_3") (pintype "bidirectional"))
    )
    (net (code "93") (name "Net-(U1-PF0)") (class "Default")
      (node (ref "C26") (pin "2") (pinfunction "2_2") (pintype "passive"))
      (node (ref "Q1") (pin "1") (pinfunction "1_1") (pintype "passive"))
      (node (ref "U1") (pin "5") (pinfunction "PF0_5") (pintype "bidirectional"))
    )
    (net (code "94") (name "Net-(U1-PF1)") (class "Default")
      (node (ref "C25") (pin "2") (pinfunction "2_2") (pintype "passive"))
      (node (ref "Q1") (pin "3") (pinfunction "3_3") (pintype "passive"))
      (node (ref "U1") (pin "6") (pinfunction "PF1_6") (pintype "bidirectional"))
    )
    (net (code "95") (name "Net-(U3-PF0)") (class "Default")
      (node (ref "C41") (pin "1") (pinfunction "1_1") (pintype "passive"))
      (node (ref "Q2") (pin "3") (pinfunction "3_3") (pintype "passive"))
      (node (ref "U3") (pin "5") (pinfunction "PF0_5") (pintype "bidirectional"))
    )
    (net (code "96") (name "Net-(U3-PF1)") (class "Default")
      (node (ref "C42") (pin "1") (pinfunction "1_1") (pintype "passive"))
      (node (ref "Q2") (pin "1") (pinfunction "1_1") (pintype "passive"))
      (node (ref "U3") (pin "6") (pinfunction "PF1_6") (pintype "bidirectional"))
    )
    (net (code "97") (name "Net-(U5-VIN)") (class "Default")
      (node (ref "C20") (pin "1") (pinfunction "1_1") (pintype "passive"))
      (node (ref "L1") (pin "2") (pinfunction "2_2") (pintype "passive"))
      (node (ref "U5") (pin "1") (pinfunction "VIN_1") (pintype "bidirectional"))
    )
    (net (code "98") (name "OUTA") (class "Default")
      (node (ref "R40") (pin "1") (pinfunction "1_1") (pintype "passive"))
      (node (ref "U$4") (pin "1") (pinfunction "OUTA_1") (pintype "bidirectional"))
    )
    (net (code "99") (name "OUTB") (class "Default")
      (node (ref "R43") (pin "1") (pinfunction "1_1") (pintype "passive"))
      (node (ref "U$4") (pin "2") (pinfunction "OUTB_2") (pintype "bidirectional"))
    )
    (net (code "100") (name "OUTC") (class "Default")
      (node (ref "R46") (pin "1") (pinfunction "1_1") (pintype "passive"))
      (node (ref "U$4") (pin "7") (pinfunction "OUTC_7") (pintype "bidirectional"))
    )
    (net (code "101") (name "OUTD") (class "Default")
      (node (ref "R49") (pin "1") (pinfunction "1_1") (pintype "passive"))
      (node (ref "U$4") (pin "8") (pinfunction "OUTD_8") (pintype "bidirectional"))
    )
    (net (code "102") (name "REF_BIAS") (class "Default")
      (node (ref "IC4") (pin "3") (pinfunction "+IN_3") (pintype "input"))
      (node (ref "IC4") (pin "5") (pinfunction "+IN_5") (pintype "input"))
      (node (ref "IC5") (pin "3") (pinfunction "+IN_3") (pintype "input"))
      (node (ref "IC5") (pin "5") (pinfunction "+IN_5") (pintype "input"))
      (node (ref "R51") (pin "1") (pinfunction "1_1") (pintype "passive"))
      (node (ref "R52") (pin "2") (pinfunction "2_2") (pintype "passive"))
    )
    (net (code "103") (name "RESET") (class "Default")
      (node (ref "C40") (pin "1") (pinfunction "1_1") (pintype "passive"))
      (node (ref "C7") (pin "1") (pinfunction "1_1") (pintype "passive"))
      (node (ref "R32") (pin "1") (pinfunction "1_1") (pintype "passive"))
      (node (ref "R50") (pin "1") (pinfunction "1_1") (pintype "passive"))
      (node (ref "SV2") (pin "4") (pinfunction "4_4") (pintype "passive"))
      (node (ref "SWD_CON") (pin "1") (pinfunction "1_1") (pintype "passive"))
      (node (ref "U1") (pin "7") (pinfunction "NRST_7") (pintype "bidirectional"))
      (node (ref "U3") (pin "7") (pinfunction "NRST_7") (pintype "bidirectional"))
    )
    (net (code "104") (name "RLED_1") (class "Default")
      (node (ref "R5") (pin "2") (pinfunction "2_2") (pintype "passive"))
      (node (ref "U1") (pin "31") (pinfunction "PA10_31") (pintype "bidirectional"))
    )
    (net (code "105") (name "RLED_2") (class "Default")
      (node (ref "R7") (pin "2") (pinfunction "2_2") (pintype "passive"))
      (node (ref "U1") (pin "10") (pinfunction "PA0_10") (pintype "bidirectional"))
    )
    (net (code "106") (name "SCR_SCL") (class "Default")
      (node (ref "U$2") (pin "3") (pinfunction "SCL_3") (pintype "bidirectional"))
      (node (ref "U1") (pin "42") (pinfunction "PB6_42") (pintype "bidirectional"))
    )
    (net (code "107") (name "SCR_SDA") (class "Default")
      (node (ref "U$2") (pin "4") (pinfunction "SDA_4") (pintype "bidirectional"))
      (node (ref "U1") (pin "43") (pinfunction "PB7_43") (pintype "bidirectional"))
    )
    (net (code "108") (name "SDADC_1") (class "Default")
      (node (ref "C1") (pin "2") (pinfunction "2_2") (pintype "passive"))
      (node (ref "R23") (pin "2") (pinfunction "2_2") (pintype "passive"))
      (node (ref "U$1") (pin "14") (pinfunction "OUT_14") (pintype "output"))
      (node (ref "U1") (pin "18") (pinfunction "PB0_18") (pintype "bidirectional"))
    )
    (net (code "109") (name "SDADC_2") (class "Default")
      (node (ref "C2") (pin "2") (pinfunction "2_2") (pintype "passive"))
      (node (ref "R25") (pin "2") (pinfunction "2_2") (pintype "passive"))
      (node (ref "U$1") (pin "8") (pinfunction "OUT_8") (pintype "output"))
      (node (ref "U1") (pin "20") (pinfunction "PB2_20") (pintype "bidirectional"))
    )
    (net (code "110") (name "SDADC_3") (class "Default")
      (node (ref "C3") (pin "2") (pinfunction "2_2") (pintype "passive"))
      (node (ref "R29") (pin "2") (pinfunction "2_2") (pintype "passive"))
      (node (ref "U$1") (pin "7") (pinfunction "OUT_7") (pintype "output"))
      (node (ref "U1") (pin "28") (pinfunction "PD8_28") (pintype "bidirectional"))
    )
    (net (code "111") (name "SPI_LDAC") (class "Default")
      (node (ref "U$4") (pin "16") (pinfunction "LDAC_16") (pintype "bidirectional"))
      (node (ref "U3") (pin "26") (pinfunction "PB14_26") (pintype "bidirectional"))
    )
    (net (code "112") (name "SPI_MOSI") (class "Default")
      (node (ref "U$4") (pin "11") (pinfunction "DIN_11") (pintype "bidirectional"))
      (node (ref "U3") (pin "27") (pinfunction "PB15_27") (pintype "bidirectional"))
    )
    (net (code "113") (name "SPI_SCK") (class "Default")
      (node (ref "U$4") (pin "10") (pinfunction "SCLK_10") (pintype "bidirectional"))
      (node (ref "U3") (pin "28") (pinfunction "PD8_28") (pintype "bidirectional"))
    )
    (net (code "114") (name "SPI_SYNC") (class "Default")
      (node (ref "U$4") (pin "9") (pinfunction "__SYNC_9") (pintype "bidirectional"))
      (node (ref "U3") (pin "29") (pinfunction "PA8_29") (pintype "bidirectional"))
    )
    (net (code "115") (name "SWCLK") (class "Default")
      (node (ref "SV2") (pin "3") (pinfunction "3_3") (pintype "passive"))
      (node (ref "SWD_CON") (pin "2") (pinfunction "2_2") (pintype "passive"))
      (node (ref "U1") (pin "37") (pinfunction "PA14_37") (pintype "bidirectional"))
      (node (ref "U3") (pin "37") (pinfunction "PA14_37") (pintype "bidirectional"))
    )
    (net (code "116") (name "SWDIO") (class "Default")
      (node (ref "SV2") (pin "2") (pinfunction "2_2") (pintype "passive"))
      (node (ref "SWD_CON") (pin "3") (pinfunction "3_3") (pintype "passive"))
      (node (ref "U1") (pin "34") (pinfunction "PA13_34") (pintype "bidirectional"))
      (node (ref "U3") (pin "34") (pinfunction "PA13_34") (pintype "bidirectional"))
    )
    (net (code "117") (name "SW_1") (class "Default")
      (node (ref "S1") (pin "P$1") (pinfunction "1_P$1") (pintype "bidirectional"))
      (node (ref "S1") (pin "P$2") (pinfunction "2_P$2") (pintype "bidirectional"))
      (node (ref "U1") (pin "21") (pinfunction "PE8_21") (pintype "bidirectional"))
    )
    (net (code "118") (name "SW_2") (class "Default")
      (node (ref "S2") (pin "P$1") (pinfunction "1_P$1") (pintype "bidirectional"))
      (node (ref "S2") (pin "P$2") (pinfunction "2_P$2") (pintype "bidirectional"))
      (node (ref "U1") (pin "15") (pinfunction "PA5_15") (pintype "bidirectional"))
    )
    (net (code "119") (name "SW_3") (class "Default")
      (node (ref "S3") (pin "P$3") (pinfunction "3_P$3") (pintype "bidirectional"))
      (node (ref "S3") (pin "P$4") (pinfunction "4_P$4") (pintype "bidirectional"))
      (node (ref "U1") (pin "13") (pinfunction "PA3_13") (pintype "bidirectional"))
    )
    (net (code "120") (name "USB_DM") (class "Default")
      (node (ref "J1") (pin "2") (pinfunction "D-_2") (pintype "bidirectional"))
      (node (ref "U3") (pin "32") (pinfunction "PA11_32") (pintype "bidirectional"))
    )
    (net (code "121") (name "USB_DP") (class "Default")
      (node (ref "J1") (pin "3") (pinfunction "D+_3") (pintype "bidirectional"))
      (node (ref "U3") (pin "33") (pinfunction "PA12_33") (pintype "bidirectional"))
    )
    (net (code "122") (name "VCC") (class "Default")
      (node (ref "C12") (pin "2") (pinfunction "2_2") (pintype "passive"))
      (node (ref "C13") (pin "2") (pinfunction "2_2") (pintype "passive"))
      (node (ref "C14") (pin "2") (pinfunction "2_2") (pintype "passive"))
      (node (ref "C15") (pin "2") (pinfunction "2_2") (pintype "passive"))
      (node (ref "C16") (pin "1") (pinfunction "1_1") (pintype "passive"))
      (node (ref "C29") (pin "2") (pinfunction "2_2") (pintype "passive"))
      (node (ref "U$1") (pin "4") (pinfunction "V+_4") (pintype "power_in"))
      (node (ref "U$3") (pin "1") (pinfunction "VOUT_1") (pintype "bidirectional"))
      (node (ref "U1") (pin "24") (pinfunction "VDDSD_24") (pintype "bidirectional"))
      (node (ref "U1") (pin "25") (pinfunction "VDDREF_25") (pintype "bidirectional"))
      (node (ref "U1") (pin "9") (pinfunction "VDDA_9") (pintype "bidirectional"))
    )
    (net (code "123") (name "VCCIO") (class "Default")
      (node (ref "C10") (pin "2") (pinfunction "2_2") (pintype "passive"))
      (node (ref "C11") (pin "2") (pinfunction "2_2") (pintype "passive"))
      (node (ref "C18") (pin "2") (pinfunction "2_2") (pintype "passive"))
      (node (ref "C19") (pin "1") (pinfunction "1_1") (pintype "passive"))
      (node (ref "C32") (pin "2") (pinfunction "2_2") (pintype "passive"))
      (node (ref "C35") (pin "1") (pinfunction "1_1") (pintype "passive"))
      (node (ref "C47") (pin "1") (pinfunction "1_1") (pintype "passive"))
      (node (ref "C48") (pin "1") (pinfunction "1_1") (pintype "passive"))
      (node (ref "C49") (pin "1") (pinfunction "1_1") (pintype "passive"))
      (node (ref "C50") (pin "1") (pinfunction "1_1") (pintype "passive"))
      (node (ref "C57") (pin "1") (pinfunction "1_1") (pintype "passive"))
      (node (ref "C8") (pin "2") (pinfunction "2_2") (pintype "passive"))
      (node (ref "C9") (pin "2") (pinfunction "2_2") (pintype "passive"))
      (node (ref "R32") (pin "2") (pinfunction "2_2") (pintype "passive"))
      (node (ref "R50") (pin "2") (pinfunction "2_2") (pintype "passive"))
      (node (ref "U$2") (pin "2") (pinfunction "VCC_2") (pintype "power_in"))
      (node (ref "U$4") (pin "12") (pinfunction "DVDD_12") (pintype "bidirectional"))
      (node (ref "U$4") (pin "13") (pinfunction "__RST_13") (pintype "bidirectional"))
      (node (ref "U$5") (pin "1") (pinfunction "VOUT_1") (pintype "bidirectional"))
      (node (ref "U1") (pin "1") (pinfunction "VBAT_1") (pintype "bidirectional"))
      (node (ref "U1") (pin "17") (pinfunction "VDD2_17") (pintype "bidirectional"))
      (node (ref "U1") (pin "48") (pinfunction "VDD1_48") (pintype "bidirectional"))
      (node (ref "U3") (pin "1") (pinfunction "VBAT_1") (pintype "bidirectional"))
      (node (ref "U3") (pin "17") (pinfunction "VDD2_17") (pintype "bidirectional"))
      (node (ref "U3") (pin "24") (pinfunction "VDDSD_24") (pintype "bidirectional"))
      (node (ref "U3") (pin "25") (pinfunction "VDDREF_25") (pintype "bidirectional"))
      (node (ref "U3") (pin "48") (pinfunction "VDD1_48") (pintype "bidirectional"))
      (node (ref "U3") (pin "9") (pinfunction "VDDA_9") (pintype "bidirectional"))
      (node (ref "U5") (pin "3") (pinfunction "VOUT_3") (pintype "bidirectional"))
    )
    (net (code "124") (name "VREF_-10") (class "Default")
      (node (ref "C24") (pin "2") (pinfunction "2_2") (pintype "passive"))
      (node (ref "R26") (pin "1") (pinfunction "1_1") (pintype "passive"))
      (node (ref "R28") (pin "1") (pinfunction "1_1") (pintype "passive"))
      (node (ref "R31") (pin "1") (pinfunction "1_1") (pintype "passive"))
      (node (ref "R33") (pin "1") (pinfunction "1_1") (pintype "passive"))
      (node (ref "U2") (pin "2") (pinfunction "A_2") (pintype "passive"))
      (node (ref "U2") (pin "3") (pinfunction "A_3") (pintype "passive"))
    )
    (net (code "125") (name "unconnected-(J1-VBUS-Pad1)") (class "Default")
      (node (ref "J1") (pin "1") (pinfunction "VBUS_1") (pintype "bidirectional"))
    )
    (net (code "126") (name "unconnected-(JCK1-SWITCH-PadP$2_SWITCH)") (class "Default")
      (node (ref "JCK1") (pin "P$2_SWITCH") (pinfunction "SWITCH_P$2_SWITCH") (pintype "passive"))
    )
    (net (code "127") (name "unconnected-(JCK2-SWITCH-PadP$2_SWITCH)") (class "Default")
      (node (ref "JCK2") (pin "P$2_SWITCH") (pinfunction "SWITCH_P$2_SWITCH") (pintype "passive"))
    )
    (net (code "128") (name "unconnected-(JCK3-SWITCH-PadP$2_SWITCH)") (class "Default")
      (node (ref "JCK3") (pin "P$2_SWITCH") (pinfunction "SWITCH_P$2_SWITCH") (pintype "passive"))
    )
    (net (code "129") (name "unconnected-(JCK4-SWITCH-PadP$2_SWITCH)") (class "Default")
      (node (ref "JCK4") (pin "P$2_SWITCH") (pinfunction "SWITCH_P$2_SWITCH") (pintype "passive"))
    )
    (net (code "130") (name "unconnected-(JCK5-SWITCH-PadP$2_SWITCH)") (class "Default")
      (node (ref "JCK5") (pin "P$2_SWITCH") (pinfunction "SWITCH_P$2_SWITCH") (pintype "passive"))
    )
    (net (code "131") (name "unconnected-(JCK6-SWITCH-PadP$2_SWITCH)") (class "Default")
      (node (ref "JCK6") (pin "P$2_SWITCH") (pinfunction "SWITCH_P$2_SWITCH") (pintype "passive"))
    )
    (net (code "132") (name "unconnected-(JCK7-SWITCH-PadP$2_SWITCH)") (class "Default")
      (node (ref "JCK7") (pin "P$2_SWITCH") (pinfunction "SWITCH_P$2_SWITCH") (pintype "passive"))
    )
    (net (code "133") (name "unconnected-(JCK8-SWITCH-PadP$2_SWITCH)") (class "Default")
      (node (ref "JCK8") (pin "P$2_SWITCH") (pinfunction "SWITCH_P$2_SWITCH") (pintype "passive"))
    )
    (net (code "134") (name "unconnected-(JCK9-SWITCH-PadP$2_SWITCH)") (class "Default")
      (node (ref "JCK9") (pin "P$2_SWITCH") (pinfunction "SWITCH_P$2_SWITCH") (pintype "passive"))
    )
    (net (code "135") (name "unconnected-(JCK10-SWITCH-PadP$2_SWITCH)") (class "Default")
      (node (ref "JCK10") (pin "P$2_SWITCH") (pinfunction "SWITCH_P$2_SWITCH") (pintype "passive"))
    )
    (net (code "136") (name "unconnected-(JCK11-SWITCH-PadP$2_SWITCH)") (class "Default")
      (node (ref "JCK11") (pin "P$2_SWITCH") (pinfunction "SWITCH_P$2_SWITCH") (pintype "passive"))
    )
    (net (code "137") (name "unconnected-(JCK12-SWITCH-PadP$2_SWITCH)") (class "Default")
      (node (ref "JCK12") (pin "P$2_SWITCH") (pinfunction "SWITCH_P$2_SWITCH") (pintype "passive"))
    )
    (net (code "138") (name "unconnected-(JCK13-SWITCH-PadP$2_SWITCH)") (class "Default")
      (node (ref "JCK13") (pin "P$2_SWITCH") (pinfunction "SWITCH_P$2_SWITCH") (pintype "passive"))
    )
    (net (code "139") (name "unconnected-(JCK14-SWITCH-PadP$2_SWITCH)") (class "Default")
      (node (ref "JCK14") (pin "P$2_SWITCH") (pinfunction "SWITCH_P$2_SWITCH") (pintype "passive"))
    )
    (net (code "140") (name "unconnected-(U1-PA2-Pad12)") (class "Default")
      (node (ref "U1") (pin "12") (pinfunction "PA2_12") (pintype "bidirectional"))
    )
    (net (code "141") (name "unconnected-(U1-PA8-Pad29)") (class "Default")
      (node (ref "U1") (pin "29") (pinfunction "PA8_29") (pintype "bidirectional"))
    )
    (net (code "142") (name "unconnected-(U1-PA15-Pad38)") (class "Default")
      (node (ref "U1") (pin "38") (pinfunction "PA15_38") (pintype "bidirectional"))
    )
    (net (code "143") (name "unconnected-(U1-PB3-Pad39)") (class "Default")
      (node (ref "U1") (pin "39") (pinfunction "PB3_39") (pintype "bidirectional"))
    )
    (net (code "144") (name "unconnected-(U1-PB4-Pad40)") (class "Default")
      (node (ref "U1") (pin "40") (pinfunction "PB4_40") (pintype "bidirectional"))
    )
    (net (code "145") (name "unconnected-(U1-PB5-Pad41)") (class "Default")
      (node (ref "U1") (pin "41") (pinfunction "PB5_41") (pintype "bidirectional"))
    )
    (net (code "146") (name "unconnected-(U1-PB8-Pad45)") (class "Default")
      (node (ref "U1") (pin "45") (pinfunction "PB8_45") (pintype "bidirectional"))
    )
    (net (code "147") (name "unconnected-(U1-PB9-Pad46)") (class "Default")
      (node (ref "U1") (pin "46") (pinfunction "PB9_46") (pintype "bidirectional"))
    )
    (net (code "148") (name "unconnected-(U1-PB14-Pad26)") (class "Default")
      (node (ref "U1") (pin "26") (pinfunction "PB14_26") (pintype "bidirectional"))
    )
    (net (code "149") (name "unconnected-(U1-PB15-Pad27)") (class "Default")
      (node (ref "U1") (pin "27") (pinfunction "PB15_27") (pintype "bidirectional"))
    )
    (net (code "150") (name "unconnected-(U1-PC13-Pad2)") (class "Default")
      (node (ref "U1") (pin "2") (pinfunction "PC13_2") (pintype "bidirectional"))
    )
    (net (code "151") (name "unconnected-(U1-PC14-Pad3)") (class "Default")
      (node (ref "U1") (pin "3") (pinfunction "PC14_3") (pintype "bidirectional"))
    )
    (net (code "152") (name "unconnected-(U1-PC15-Pad4)") (class "Default")
      (node (ref "U1") (pin "4") (pinfunction "PC15_4") (pintype "bidirectional"))
    )
    (net (code "153") (name "unconnected-(U1-PF6-Pad35)") (class "Default")
      (node (ref "U1") (pin "35") (pinfunction "PF6_35") (pintype "bidirectional"))
    )
    (net (code "154") (name "unconnected-(U1-PF7-Pad36)") (class "Default")
      (node (ref "U1") (pin "36") (pinfunction "PF7_36") (pintype "bidirectional"))
    )
    (net (code "155") (name "unconnected-(U3-PA0-Pad10)") (class "Default")
      (node (ref "U3") (pin "10") (pinfunction "PA0_10") (pintype "bidirectional"))
    )
    (net (code "156") (name "unconnected-(U3-PA9-Pad30)") (class "Default")
      (node (ref "U3") (pin "30") (pinfunction "PA9_30") (pintype "bidirectional"))
    )
    (net (code "157") (name "unconnected-(U3-PA10-Pad31)") (class "Default")
      (node (ref "U3") (pin "31") (pinfunction "PA10_31") (pintype "bidirectional"))
    )
    (net (code "158") (name "unconnected-(U3-PA15-Pad38)") (class "Default")
      (node (ref "U3") (pin "38") (pinfunction "PA15_38") (pintype "bidirectional"))
    )
    (net (code "159") (name "unconnected-(U3-PB2-Pad20)") (class "Default")
      (node (ref "U3") (pin "20") (pinfunction "PB2_20") (pintype "bidirectional"))
    )
    (net (code "160") (name "unconnected-(U3-PB3-Pad39)") (class "Default")
      (node (ref "U3") (pin "39") (pinfunction "PB3_39") (pintype "bidirectional"))
    )
    (net (code "161") (name "unconnected-(U3-PB4-Pad40)") (class "Default")
      (node (ref "U3") (pin "40") (pinfunction "PB4_40") (pintype "bidirectional"))
    )
    (net (code "162") (name "unconnected-(U3-PB5-Pad41)") (class "Default")
      (node (ref "U3") (pin "41") (pinfunction "PB5_41") (pintype "bidirectional"))
    )
    (net (code "163") (name "unconnected-(U3-PC13-Pad2)") (class "Default")
      (node (ref "U3") (pin "2") (pinfunction "PC13_2") (pintype "bidirectional"))
    )
    (net (code "164") (name "unconnected-(U3-PC14-Pad3)") (class "Default")
      (node (ref "U3") (pin "3") (pinfunction "PC14_3") (pintype "bidirectional"))
    )
    (net (code "165") (name "unconnected-(U3-PC15-Pad4)") (class "Default")
      (node (ref "U3") (pin "4") (pinfunction "PC15_4") (pintype "bidirectional"))
    )
    (net (code "166") (name "unconnected-(U3-PE8-Pad21)") (class "Default")
      (node (ref "U3") (pin "21") (pinfunction "PE8_21") (pintype "bidirectional"))
    )
    (net (code "167") (name "unconnected-(U3-PE9-Pad22)") (class "Default")
      (node (ref "U3") (pin "22") (pinfunction "PE9_22") (pintype "bidirectional"))
    )
    (net (code "168") (name "unconnected-(U3-PF6-Pad35)") (class "Default")
      (node (ref "U3") (pin "35") (pinfunction "PF6_35") (pintype "bidirectional"))
    )
    (net (code "169") (name "unconnected-(U3-PF7-Pad36)") (class "Default")
      (node (ref "U3") (pin "36") (pinfunction "PF7_36") (pintype "bidirectional"))
    )
  )
)
